# bontor_mbed_rev_f.net
KiCad netlist of a schematic drawn in EAGLE
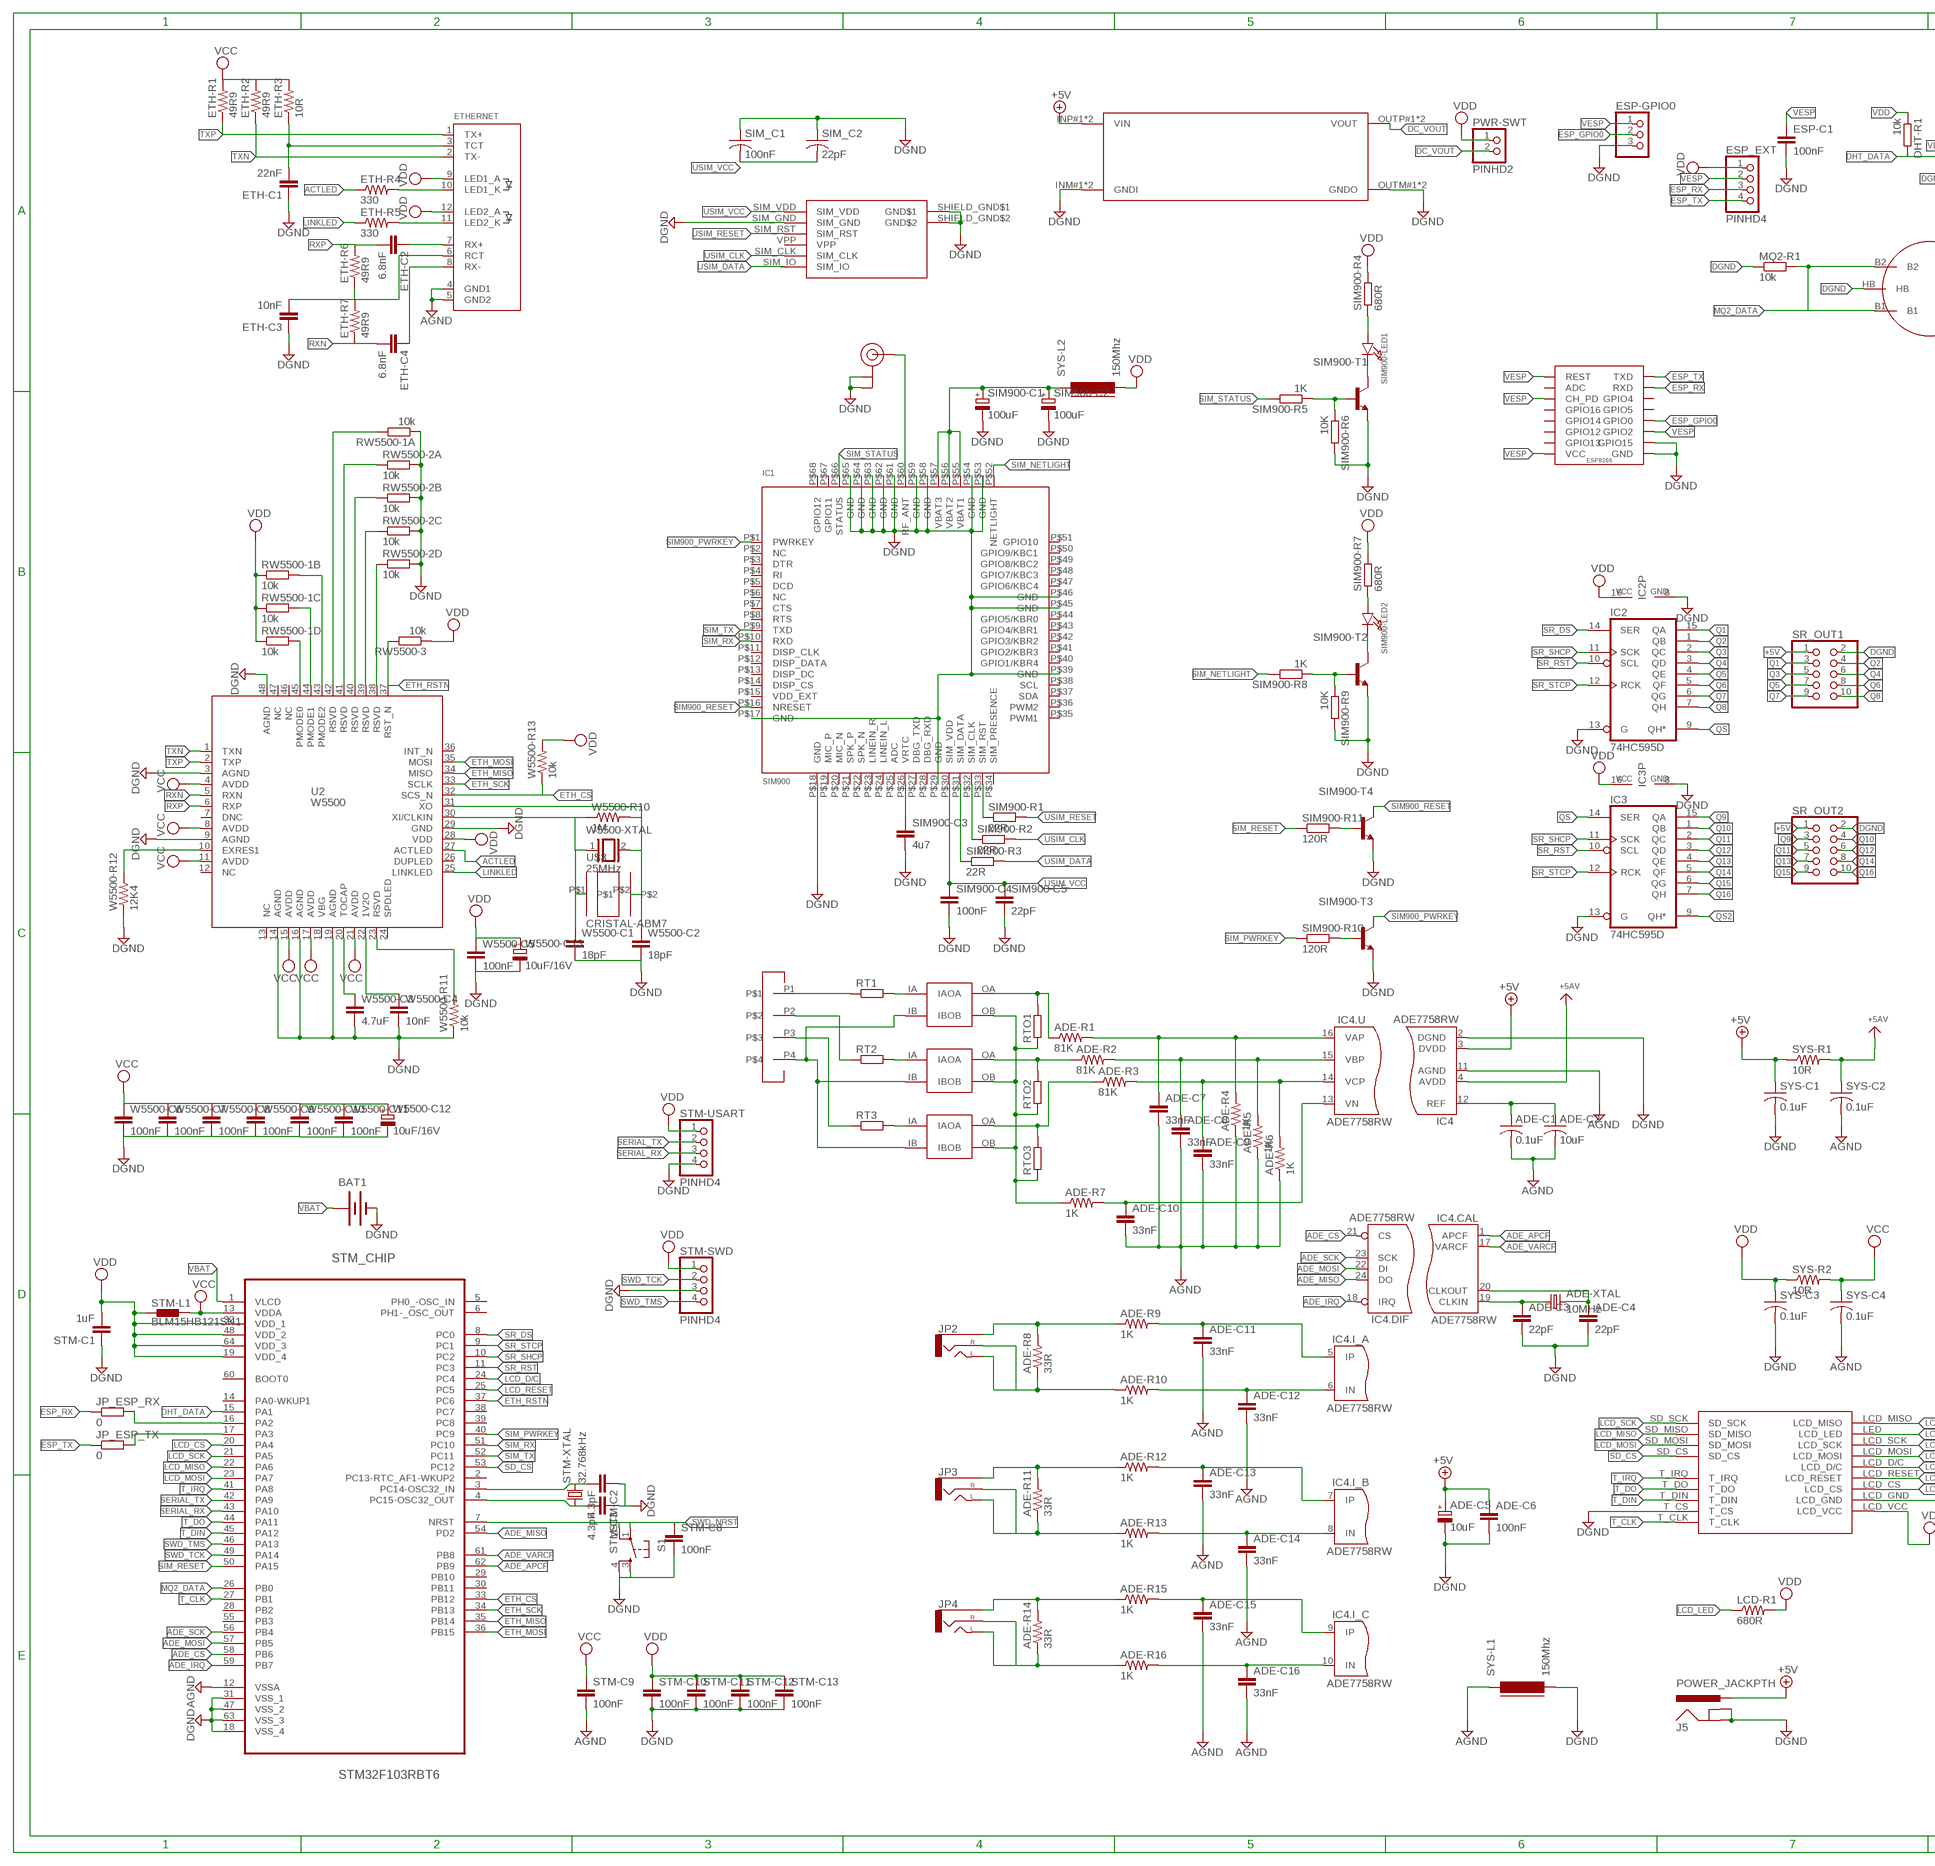
[diagram p0: schematic, sheet 1, part 1 of 2]
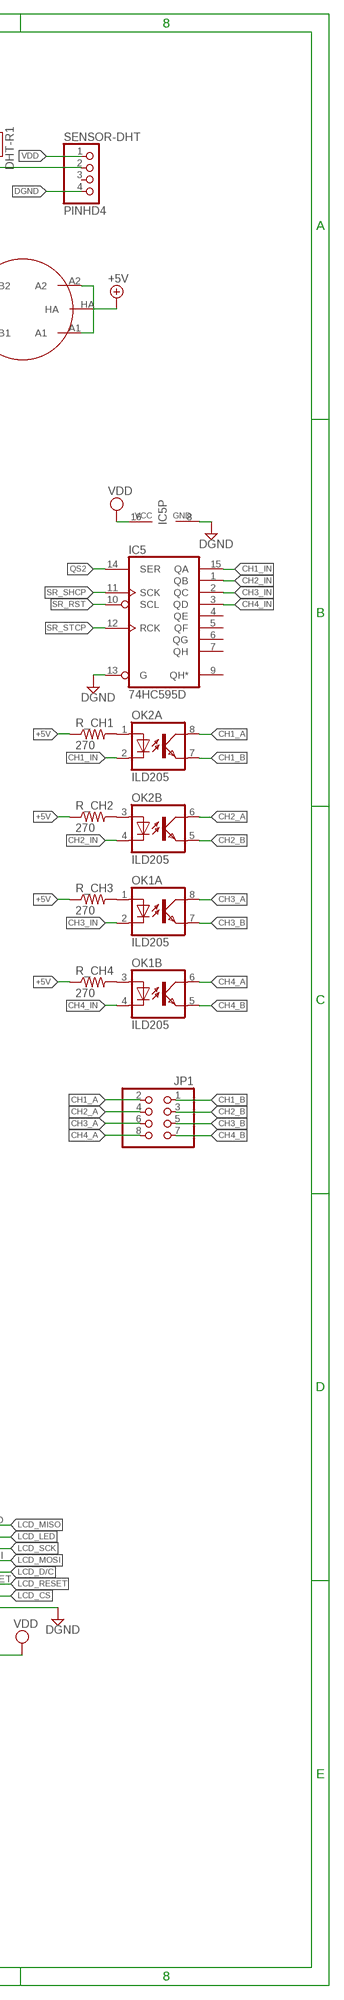
[diagram p1: schematic, sheet 1, part 2 of 2]

(export (version "E")
  (design (tool "Eeschema 10.0.6"))
  (components
    (comp (ref "ADE-C1")
      (value "0.1uF")
      (footprint "eagle-import:C0603@1")
      (libsource (lib "eagle-import") (part "C-USC0603"))
    )
    (comp (ref "ADE-C2")
      (value "10uF")
      (footprint "eagle-import:C0805K")
      (libsource (lib "eagle-import") (part "C-USC0805K"))
    )
    (comp (ref "ADE-C3")
      (value "22pF")
      (footprint "eagle-import:C0603")
      (libsource (lib "eagle-import") (part "C-EUC0603"))
    )
    (comp (ref "ADE-C4")
      (value "22pF")
      (footprint "eagle-import:C0603")
      (libsource (lib "eagle-import") (part "C-EUC0603"))
    )
    (comp (ref "ADE-C5")
      (value "10uF")
      (footprint "eagle-import:153CLV-0605")
      (libsource (lib "eagle-import") (part "CPOL-EU153CLV-0605"))
    )
    (comp (ref "ADE-C6")
      (value "100nF")
      (footprint "eagle-import:C0603")
      (libsource (lib "eagle-import") (part "C-EUC0603"))
    )
    (comp (ref "ADE-C7")
      (value "33nF")
      (footprint "eagle-import:0603-CAP")
      (libsource (lib "eagle-import") (part "CAP0603-CAP"))
    )
    (comp (ref "ADE-C8")
      (value "33nF")
      (footprint "eagle-import:0603-CAP")
      (libsource (lib "eagle-import") (part "CAP0603-CAP"))
    )
    (comp (ref "ADE-C9")
      (value "33nF")
      (footprint "eagle-import:0603-CAP")
      (libsource (lib "eagle-import") (part "CAP0603-CAP"))
    )
    (comp (ref "ADE-C10")
      (value "33nF")
      (footprint "eagle-import:0603-CAP")
      (libsource (lib "eagle-import") (part "CAP0603-CAP"))
    )
    (comp (ref "ADE-C11")
      (value "33nF")
      (footprint "eagle-import:0603-CAP")
      (libsource (lib "eagle-import") (part "CAP0603-CAP"))
    )
    (comp (ref "ADE-C12")
      (value "33nF")
      (footprint "eagle-import:0603-CAP")
      (libsource (lib "eagle-import") (part "CAP0603-CAP"))
    )
    (comp (ref "ADE-C13")
      (value "33nF")
      (footprint "eagle-import:0603-CAP")
      (libsource (lib "eagle-import") (part "CAP0603-CAP"))
    )
    (comp (ref "ADE-C14")
      (value "33nF")
      (footprint "eagle-import:0603-CAP")
      (libsource (lib "eagle-import") (part "CAP0603-CAP"))
    )
    (comp (ref "ADE-C15")
      (value "33nF")
      (footprint "eagle-import:0603-CAP")
      (libsource (lib "eagle-import") (part "CAP0603-CAP"))
    )
    (comp (ref "ADE-C16")
      (value "33nF")
      (footprint "eagle-import:0603-CAP")
      (libsource (lib "eagle-import") (part "CAP0603-CAP"))
    )
    (comp (ref "ADE-R1")
      (value "81K")
      (footprint "eagle-import:0603-RES")
      (libsource (lib "eagle-import") (part "RESISTOR0603-RES"))
    )
    (comp (ref "ADE-R2")
      (value "81K")
      (footprint "eagle-import:0603-RES")
      (libsource (lib "eagle-import") (part "RESISTOR0603-RES"))
    )
    (comp (ref "ADE-R3")
      (value "81K")
      (footprint "eagle-import:0603-RES")
      (libsource (lib "eagle-import") (part "RESISTOR0603-RES"))
    )
    (comp (ref "ADE-R4")
      (value "1K")
      (footprint "eagle-import:0603-RES")
      (libsource (lib "eagle-import") (part "RESISTOR0603-RES"))
    )
    (comp (ref "ADE-R5")
      (value "1K")
      (footprint "eagle-import:0603-RES")
      (libsource (lib "eagle-import") (part "RESISTOR0603-RES"))
    )
    (comp (ref "ADE-R6")
      (value "1K")
      (footprint "eagle-import:0603-RES")
      (libsource (lib "eagle-import") (part "RESISTOR0603-RES"))
    )
    (comp (ref "ADE-R7")
      (value "1K")
      (footprint "eagle-import:0603-RES")
      (libsource (lib "eagle-import") (part "RESISTOR0603-RES"))
    )
    (comp (ref "ADE-R8")
      (value "33R")
      (footprint "eagle-import:0603-RES")
      (libsource (lib "eagle-import") (part "RESISTOR0603-RES"))
    )
    (comp (ref "ADE-R9")
      (value "1K")
      (footprint "eagle-import:0603-RES")
      (libsource (lib "eagle-import") (part "RESISTOR0603-RES"))
    )
    (comp (ref "ADE-R10")
      (value "1K")
      (footprint "eagle-import:0603-RES")
      (libsource (lib "eagle-import") (part "RESISTOR0603-RES"))
    )
    (comp (ref "ADE-R11")
      (value "33R")
      (footprint "eagle-import:0603-RES")
      (libsource (lib "eagle-import") (part "RESISTOR0603-RES"))
    )
    (comp (ref "ADE-R12")
      (value "1K")
      (footprint "eagle-import:0603-RES")
      (libsource (lib "eagle-import") (part "RESISTOR0603-RES"))
    )
    (comp (ref "ADE-R13")
      (value "1K")
      (footprint "eagle-import:0603-RES")
      (libsource (lib "eagle-import") (part "RESISTOR0603-RES"))
    )
    (comp (ref "ADE-R14")
      (value "33R")
      (footprint "eagle-import:0603-RES")
      (libsource (lib "eagle-import") (part "RESISTOR0603-RES"))
    )
    (comp (ref "ADE-R15")
      (value "1K")
      (footprint "eagle-import:0603-RES")
      (libsource (lib "eagle-import") (part "RESISTOR0603-RES"))
    )
    (comp (ref "ADE-R16")
      (value "1K")
      (footprint "eagle-import:0603-RES")
      (libsource (lib "eagle-import") (part "RESISTOR0603-RES"))
    )
    (comp (ref "ADE-XTAL")
      (value "10MHz")
      (footprint "eagle-import:HC49US")
      (libsource (lib "eagle-import") (part "CRYSTALHC49US"))
    )
    (comp (ref "BAT1")
      (value "BATTERY12MM")
      (footprint "eagle-import:BATTCON_12MM")
      (libsource (lib "eagle-import") (part "BATTERY12MM"))
    )
    (comp (ref "DCDC-3.5V")
      (value "DCDCMODULE_SMALL")
      (footprint "eagle-import:DCDCMODULE-SMALL")
      (libsource (lib "eagle-import") (part "DCDCMODULE_SMALL"))
    )
    (comp (ref "DHT-R1")
      (value "10k")
      (footprint "eagle-import:R0603")
      (libsource (lib "eagle-import") (part "resistor_R-EU_R0603"))
    )
    (comp (ref "ESP-C1")
      (value "100nF")
      (footprint "eagle-import:C0603")
      (libsource (lib "eagle-import") (part "C-EUC0603"))
    )
    (comp (ref "ESP-GPIO0")
      (value "PINHD-1X3")
      (footprint "eagle-import:1X03")
      (libsource (lib "eagle-import") (part "PINHD-1X3"))
    )
    (comp (ref "ESP_EXT")
      (value "PINHD4")
      (footprint "eagle-import:PINHD4")
      (libsource (lib "eagle-import") (part "PINHD4"))
    )
    (comp (ref "ETH-C1")
      (value "22nF")
      (footprint "eagle-import:C0603")
      (libsource (lib "eagle-import") (part "C-EUC0603"))
    )
    (comp (ref "ETH-C2")
      (value "6.8nF")
      (footprint "eagle-import:C0603")
      (libsource (lib "eagle-import") (part "C-EUC0603"))
    )
    (comp (ref "ETH-C3")
      (value "10nF")
      (footprint "eagle-import:C0603")
      (libsource (lib "eagle-import") (part "C-EUC0603"))
    )
    (comp (ref "ETH-C4")
      (value "6.8nF")
      (footprint "eagle-import:C0603")
      (libsource (lib "eagle-import") (part "C-EUC0603"))
    )
    (comp (ref "ETH-R1")
      (value "49R9")
      (footprint "eagle-import:R0603")
      (libsource (lib "eagle-import") (part "R-US_R0603"))
    )
    (comp (ref "ETH-R2")
      (value "49R9")
      (footprint "eagle-import:R0603")
      (libsource (lib "eagle-import") (part "R-US_R0603"))
    )
    (comp (ref "ETH-R3")
      (value "10R")
      (footprint "eagle-import:R0603")
      (libsource (lib "eagle-import") (part "R-US_R0603"))
    )
    (comp (ref "ETH-R4")
      (value "330")
      (footprint "eagle-import:R0603")
      (libsource (lib "eagle-import") (part "R-US_R0603"))
    )
    (comp (ref "ETH-R5")
      (value "330")
      (footprint "eagle-import:R0603")
      (libsource (lib "eagle-import") (part "R-US_R0603"))
    )
    (comp (ref "ETH-R6")
      (value "49R9")
      (footprint "eagle-import:R0603")
      (libsource (lib "eagle-import") (part "R-US_R0603"))
    )
    (comp (ref "ETH-R7")
      (value "49R9")
      (footprint "eagle-import:R0603")
      (libsource (lib "eagle-import") (part "R-US_R0603"))
    )
    (comp (ref "ETHERNET")
      (value "RJ45J0026D21BNL")
      (footprint "eagle-import:RJ45_PULSEJACK")
      (libsource (lib "eagle-import") (part "RJ45J0026D21BNL"))
    )
    (comp (ref "IC1")
      (value "SIM900")
      (footprint "eagle-import:SIM900_SMT")
      (libsource (lib "eagle-import") (part "GSM_SIM900_LITERAL"))
    )
    (comp (ref "IC2")
      (value "74HC595D")
      (footprint "eagle-import:SO16")
      (libsource (lib "eagle-import") (part "74595DHC"))
    )
    (comp (ref "IC3")
      (value "74HC595D")
      (footprint "eagle-import:SO16")
      (libsource (lib "eagle-import") (part "74595DHC"))
    )
    (comp (ref "IC4")
      (value "ADE7758RW")
      (footprint "eagle-import:SOIC24")
      (libsource (lib "eagle-import") (part "ADE7758RW"))
    )
    (comp (ref "IC5")
      (value "74HC595D")
      (footprint "eagle-import:SO16")
      (libsource (lib "eagle-import") (part "74595DHC"))
    )
    (comp (ref "J5")
      (value "POWER_JACKPTH")
      (footprint "eagle-import:POWER_JACK_PTH")
      (libsource (lib "eagle-import") (part "POWER_JACKPTH"))
    )
    (comp (ref "JP1")
      (value "PINHD-2X4")
      (footprint "eagle-import:2X04")
      (libsource (lib "eagle-import") (part "PINHD-2X4"))
    )
    (comp (ref "JP2")
      (value "AUDIO-JACKSMD2")
      (footprint "eagle-import:AUDIO-JACK-3.5MM-SMD")
      (libsource (lib "eagle-import") (part "AUDIO-JACKSMD2"))
    )
    (comp (ref "JP3")
      (value "AUDIO-JACKSMD2")
      (footprint "eagle-import:AUDIO-JACK-3.5MM-SMD")
      (libsource (lib "eagle-import") (part "AUDIO-JACKSMD2"))
    )
    (comp (ref "JP4")
      (value "AUDIO-JACKSMD2")
      (footprint "eagle-import:AUDIO-JACK-3.5MM-SMD")
      (libsource (lib "eagle-import") (part "AUDIO-JACKSMD2"))
    )
    (comp (ref "JP_ESP_RX")
      (value "0")
      (footprint "eagle-import:R0201")
      (libsource (lib "eagle-import") (part "R-EU_R0201"))
    )
    (comp (ref "JP_ESP_TX")
      (value "0")
      (footprint "eagle-import:R0201")
      (libsource (lib "eagle-import") (part "R-EU_R0201"))
    )
    (comp (ref "LCD-R1")
      (value "680R")
      (footprint "eagle-import:0603-RES")
      (libsource (lib "eagle-import") (part "RESISTOR0603-RES"))
    )
    (comp (ref "MQ2-R1")
      (value "10k")
      (footprint "eagle-import:R0603")
      (libsource (lib "eagle-import") (part "resistor_R-EU_R0603"))
    )
    (comp (ref "OK1")
      (value "ILD205")
      (footprint "eagle-import:SOIC08")
      (fields (field (name "MF") "VISHAY/TELEFUNKEN") (field (name "MPN") "ILD205T"))
      (libsource (lib "eagle-import") (part "ILD205"))
    )
    (comp (ref "OK2")
      (value "ILD205")
      (footprint "eagle-import:SOIC08")
      (fields (field (name "MF") "VISHAY/TELEFUNKEN") (field (name "MPN") "ILD205T"))
      (libsource (lib "eagle-import") (part "ILD205"))
    )
    (comp (ref "PWR-SWT")
      (value "PINHD2")
      (footprint "eagle-import:PINHD2")
      (libsource (lib "eagle-import") (part "PINHD2"))
    )
    (comp (ref "RT1")
      (value "R-EU_0309/V")
      (footprint "eagle-import:0309V")
      (libsource (lib "eagle-import") (part "R-EU_0309/V"))
    )
    (comp (ref "RT2")
      (value "R-EU_0309/V")
      (footprint "eagle-import:0309V")
      (libsource (lib "eagle-import") (part "R-EU_0309/V"))
    )
    (comp (ref "RT3")
      (value "R-EU_0309/V")
      (footprint "eagle-import:0309V")
      (libsource (lib "eagle-import") (part "R-EU_0309/V"))
    )
    (comp (ref "RTO1")
      (value "R-EU_0309/12")
      (footprint "eagle-import:0309_12")
      (libsource (lib "eagle-import") (part "R-EU_0309/12"))
    )
    (comp (ref "RTO2")
      (value "R-EU_0309/12")
      (footprint "eagle-import:0309_12")
      (libsource (lib "eagle-import") (part "R-EU_0309/12"))
    )
    (comp (ref "RTO3")
      (value "R-EU_0309/12")
      (footprint "eagle-import:0309_12")
      (libsource (lib "eagle-import") (part "R-EU_0309/12"))
    )
    (comp (ref "RW5500-1")
      (value "10k")
      (footprint "eagle-import:RN8P-4R-CRA06S")
      (libsource (lib "eagle-import") (part "RESISTOR_ARRAY_4"))
    )
    (comp (ref "RW5500-2")
      (value "10k")
      (footprint "eagle-import:RN8P-4R-CRA06S")
      (libsource (lib "eagle-import") (part "RESISTOR_ARRAY_4"))
    )
    (comp (ref "RW5500-3")
      (value "10k")
      (footprint "eagle-import:R0603")
      (libsource (lib "eagle-import") (part "R-EU_R0603"))
    )
    (comp (ref "R_CH1")
      (value "270")
      (footprint "eagle-import:0603-RES")
      (libsource (lib "eagle-import") (part "RESISTOR0603-RES"))
    )
    (comp (ref "R_CH2")
      (value "270")
      (footprint "eagle-import:0603-RES")
      (libsource (lib "eagle-import") (part "RESISTOR0603-RES"))
    )
    (comp (ref "R_CH3")
      (value "270")
      (footprint "eagle-import:0603-RES")
      (libsource (lib "eagle-import") (part "RESISTOR0603-RES"))
    )
    (comp (ref "R_CH4")
      (value "270")
      (footprint "eagle-import:0603-RES")
      (libsource (lib "eagle-import") (part "RESISTOR0603-RES"))
    )
    (comp (ref "S1")
      (value "TAC_SWITCHSMD")
      (footprint "eagle-import:TACTILE-SWITCH-SMD")
      (libsource (lib "eagle-import") (part "TAC_SWITCHSMD"))
    )
    (comp (ref "SENSOR-DHT")
      (value "PINHD4")
      (footprint "eagle-import:PINHD4")
      (libsource (lib "eagle-import") (part "PINHD4"))
    )
    (comp (ref "SENSOR-MQ2")
      (value "METHANE_SENSOR")
      (footprint "eagle-import:MQ-3")
      (libsource (lib "eagle-import") (part "METHANE_SENSOR"))
    )
    (comp (ref "SIM900-C1")
      (value "100uF")
      (footprint "eagle-import:153CLV-0605")
      (libsource (lib "eagle-import") (part "CPOL-EU153CLV-0605"))
    )
    (comp (ref "SIM900-C2")
      (value "100uF")
      (footprint "eagle-import:153CLV-0605")
      (libsource (lib "eagle-import") (part "CPOL-EU153CLV-0605"))
    )
    (comp (ref "SIM900-C3")
      (value "4u7")
      (footprint "eagle-import:C0603")
      (libsource (lib "eagle-import") (part "C-EUC0603"))
    )
    (comp (ref "SIM900-C4")
      (value "100nF")
      (footprint "eagle-import:C0603")
      (libsource (lib "eagle-import") (part "C-EUC0603"))
    )
    (comp (ref "SIM900-C5")
      (value "22pF")
      (footprint "eagle-import:C0603")
      (libsource (lib "eagle-import") (part "C-EUC0603"))
    )
    (comp (ref "SIM900-LED1")
      (value "LED0805_NOOUTLINE")
      (footprint "eagle-import:CHIPLED_0805_NOOUTLINE")
      (libsource (lib "eagle-import") (part "LED0805_NOOUTLINE"))
    )
    (comp (ref "SIM900-LED2")
      (value "LED0805_NOOUTLINE")
      (footprint "eagle-import:CHIPLED_0805_NOOUTLINE")
      (libsource (lib "eagle-import") (part "LED0805_NOOUTLINE"))
    )
    (comp (ref "SIM900-R1")
      (value "22R")
      (footprint "eagle-import:R0603")
      (libsource (lib "eagle-import") (part "R-EU_R0603"))
    )
    (comp (ref "SIM900-R2")
      (value "22R")
      (footprint "eagle-import:R0603")
      (libsource (lib "eagle-import") (part "R-EU_R0603"))
    )
    (comp (ref "SIM900-R3")
      (value "22R")
      (footprint "eagle-import:R0603")
      (libsource (lib "eagle-import") (part "R-EU_R0603"))
    )
    (comp (ref "SIM900-R4")
      (value "680R")
      (footprint "eagle-import:R0603")
      (libsource (lib "eagle-import") (part "R-EU_R0603"))
    )
    (comp (ref "SIM900-R5")
      (value "1K")
      (footprint "eagle-import:R0603")
      (libsource (lib "eagle-import") (part "R-EU_R0603"))
    )
    (comp (ref "SIM900-R6")
      (value "10K")
      (footprint "eagle-import:R0603")
      (libsource (lib "eagle-import") (part "R-EU_R0603"))
    )
    (comp (ref "SIM900-R7")
      (value "680R")
      (footprint "eagle-import:R0603")
      (libsource (lib "eagle-import") (part "R-EU_R0603"))
    )
    (comp (ref "SIM900-R8")
      (value "1K")
      (footprint "eagle-import:R0603")
      (libsource (lib "eagle-import") (part "R-EU_R0603"))
    )
    (comp (ref "SIM900-R9")
      (value "10K")
      (footprint "eagle-import:R0603")
      (libsource (lib "eagle-import") (part "R-EU_R0603"))
    )
    (comp (ref "SIM900-R10")
      (value "120R")
      (footprint "eagle-import:R0603")
      (libsource (lib "eagle-import") (part "resistor_R-EU_R0603"))
    )
    (comp (ref "SIM900-R11")
      (value "120R")
      (footprint "eagle-import:R0603")
      (libsource (lib "eagle-import") (part "resistor_R-EU_R0603"))
    )
    (comp (ref "SIM900-T1")
      (value "MMBT2222ALT1-NPN-SOT23-BEC")
      (footprint "eagle-import:SOT23-BEC")
      (libsource (lib "eagle-import") (part "-NPN-SOT23-BECMMBT2222ALT1"))
    )
    (comp (ref "SIM900-T2")
      (value "MMBT2222ALT1-NPN-SOT23-BEC")
      (footprint "eagle-import:SOT23-BEC")
      (libsource (lib "eagle-import") (part "-NPN-SOT23-BECMMBT2222ALT1"))
    )
    (comp (ref "SIM900-T3")
      (value "MMBT2222ALT1-NPN-SOT23-BEC")
      (footprint "eagle-import:SOT23-BEC")
      (libsource (lib "eagle-import") (part "transistor-neu-to92_-NPN-SOT23-BECMMBT2222ALT1"))
    )
    (comp (ref "SIM900-T4")
      (value "MMBT2222ALT1-NPN-SOT23-BEC")
      (footprint "eagle-import:SOT23-BEC")
      (libsource (lib "eagle-import") (part "transistor-neu-to92_-NPN-SOT23-BECMMBT2222ALT1"))
    )
    (comp (ref "SIM_C1")
      (value "100nF")
      (footprint "eagle-import:C0603K")
      (libsource (lib "eagle-import") (part "C-USC0603K"))
    )
    (comp (ref "SIM_C2")
      (value "22pF")
      (footprint "eagle-import:C0603K")
      (libsource (lib "eagle-import") (part "C-USC0603K"))
    )
    (comp (ref "SR_OUT1")
      (value "PINHD-2X5/90")
      (footprint "eagle-import:2X05_90")
      (libsource (lib "eagle-import") (part "PINHD-2X5/90"))
    )
    (comp (ref "SR_OUT2")
      (value "PINHD-2X5/90")
      (footprint "eagle-import:2X05_90")
      (libsource (lib "eagle-import") (part "PINHD-2X5/90"))
    )
    (comp (ref "STM-C1")
      (value "1uF")
      (footprint "eagle-import:C0603")
      (libsource (lib "eagle-import") (part "C-EUC0603"))
    )
    (comp (ref "STM-C2")
      (value "4.3pF")
      (footprint "eagle-import:C0603")
      (libsource (lib "eagle-import") (part "C-EUC0603"))
    )
    (comp (ref "STM-C3")
      (value "4.3pF")
      (footprint "eagle-import:C0603")
      (libsource (lib "eagle-import") (part "C-EUC0603"))
    )
    (comp (ref "STM-C8")
      (value "100nF")
      (footprint "eagle-import:C0603")
      (libsource (lib "eagle-import") (part "C-EUC0603"))
    )
    (comp (ref "STM-C9")
      (value "100nF")
      (footprint "eagle-import:C0603")
      (libsource (lib "eagle-import") (part "C-EUC0603"))
    )
    (comp (ref "STM-C10")
      (value "100nF")
      (footprint "eagle-import:C0603")
      (libsource (lib "eagle-import") (part "C-EUC0603"))
    )
    (comp (ref "STM-C11")
      (value "100nF")
      (footprint "eagle-import:C0603")
      (libsource (lib "eagle-import") (part "C-EUC0603"))
    )
    (comp (ref "STM-C12")
      (value "100nF")
      (footprint "eagle-import:C0603")
      (libsource (lib "eagle-import") (part "C-EUC0603"))
    )
    (comp (ref "STM-C13")
      (value "100nF")
      (footprint "eagle-import:C0603")
      (libsource (lib "eagle-import") (part "C-EUC0603"))
    )
    (comp (ref "STM-L1")
      (value "BLM15HB121SN1")
      (footprint "eagle-import:0402")
      (libsource (lib "eagle-import") (part "BLM15HB121SN1"))
    )
    (comp (ref "STM-SWD")
      (value "PINHD4")
      (footprint "eagle-import:PINHD4")
      (libsource (lib "eagle-import") (part "PINHD4"))
    )
    (comp (ref "STM-USART")
      (value "PINHD4")
      (footprint "eagle-import:PINHD4")
      (libsource (lib "eagle-import") (part "PINHD4"))
    )
    (comp (ref "STM-XTAL")
      (value "32.768kHz")
      (footprint "eagle-import:TC26H")
      (libsource (lib "eagle-import") (part "CRYSTALTC26H"))
    )
    (comp (ref "STM_CHIP")
      (value "STM32F103RBT6")
      (footprint "eagle-import:QFP50P1200X1200X160-64N")
      (fields (field (name "MPN") "STM32L152RBT6"))
      (libsource (lib "eagle-import") (part "STM32L152RBT6"))
    )
    (comp (ref "SYS-C1")
      (value "0.1uF")
      (footprint "eagle-import:C0603@1")
      (libsource (lib "eagle-import") (part "C-USC0603"))
    )
    (comp (ref "SYS-C2")
      (value "0.1uF")
      (footprint "eagle-import:C0603@1")
      (libsource (lib "eagle-import") (part "C-USC0603"))
    )
    (comp (ref "SYS-C3")
      (value "0.1uF")
      (footprint "eagle-import:C0603@1")
      (libsource (lib "eagle-import") (part "C-USC0603"))
    )
    (comp (ref "SYS-C4")
      (value "0.1uF")
      (footprint "eagle-import:C0603@1")
      (libsource (lib "eagle-import") (part "C-USC0603"))
    )
    (comp (ref "SYS-L1")
      (value "150Mhz")
      (footprint "eagle-import:FB805")
      (libsource (lib "eagle-import") (part "FERRITE-0805"))
    )
    (comp (ref "SYS-L2")
      (value "150Mhz")
      (footprint "eagle-import:FB805")
      (libsource (lib "eagle-import") (part "FERRITE-0805"))
    )
    (comp (ref "SYS-R1")
      (value "10R")
      (footprint "eagle-import:0603-RES")
      (libsource (lib "eagle-import") (part "RESISTOR0603-RES"))
    )
    (comp (ref "SYS-R2")
      (value "10R")
      (footprint "eagle-import:0603-RES")
      (libsource (lib "eagle-import") (part "RESISTOR0603-RES"))
    )
    (comp (ref "U$3")
      (value "CRISTAL-ABM7")
      (footprint "eagle-import:CRISTAL-ABM7")
      (libsource (lib "eagle-import") (part "CRISTAL-ABM7"))
    )
    (comp (ref "U$5")
      (value "ESP8266WI12")
      (footprint "eagle-import:WI12")
      (libsource (lib "eagle-import") (part "ESP8266WI12"))
    )
    (comp (ref "U$7")
      (value "U.FL")
      (footprint "eagle-import:U.FL")
      (libsource (lib "eagle-import") (part "U.FL"))
    )
    (comp (ref "U$8")
      (value "SIM_HOLDER")
      (footprint "eagle-import:SIMHOLDER-PUSHPUSH")
      (libsource (lib "eagle-import") (part "SIM_HOLDER"))
    )
    (comp (ref "U$9")
      (value "TRANSFORMER")
      (footprint "eagle-import:TV16")
      (libsource (lib "eagle-import") (part "TRANSFORMER"))
    )
    (comp (ref "U$10")
      (value "TRANSFORMER")
      (footprint "eagle-import:TV16")
      (libsource (lib "eagle-import") (part "TRANSFORMER"))
    )
    (comp (ref "U$11")
      (value "TRANSFORMER")
      (footprint "eagle-import:TV16")
      (libsource (lib "eagle-import") (part "TRANSFORMER"))
    )
    (comp (ref "U$12")
      (value "TERMINAL_BLOCK")
      (footprint "eagle-import:TERMINAL-RIGHT-ANGLE")
      (libsource (lib "eagle-import") (part "TERMINAL_BLOCK"))
    )
    (comp (ref "U$13")
      (value "LCD_2.4")
      (footprint "eagle-import:LCD_TOUCH_2-4")
      (libsource (lib "eagle-import") (part "LCD_2.4"))
    )
    (comp (ref "U2")
      (value "W5500")
      (footprint "eagle-import:W5500")
      (libsource (lib "eagle-import") (part "W5500"))
    )
    (comp (ref "W5500-C1")
      (value "18pF")
      (footprint "eagle-import:C0603")
      (libsource (lib "eagle-import") (part "C-EUC0603"))
    )
    (comp (ref "W5500-C2")
      (value "18pF")
      (footprint "eagle-import:C0603")
      (libsource (lib "eagle-import") (part "C-EUC0603"))
    )
    (comp (ref "W5500-C3")
      (value "4.7uF")
      (footprint "eagle-import:C0603")
      (libsource (lib "eagle-import") (part "C-EUC0603"))
    )
    (comp (ref "W5500-C4")
      (value "10nF")
      (footprint "eagle-import:C0603")
      (libsource (lib "eagle-import") (part "C-EUC0603"))
    )
    (comp (ref "W5500-C5")
      (value "100nF")
      (footprint "eagle-import:C0603")
      (libsource (lib "eagle-import") (part "C-EUC0603"))
    )
    (comp (ref "W5500-C6")
      (value "100nF")
      (footprint "eagle-import:C0603")
      (libsource (lib "eagle-import") (part "C-EUC0603"))
    )
    (comp (ref "W5500-C7")
      (value "100nF")
      (footprint "eagle-import:C0603")
      (libsource (lib "eagle-import") (part "C-EUC0603"))
    )
    (comp (ref "W5500-C8")
      (value "100nF")
      (footprint "eagle-import:C0603")
      (libsource (lib "eagle-import") (part "C-EUC0603"))
    )
    (comp (ref "W5500-C9")
      (value "100nF")
      (footprint "eagle-import:C0603")
      (libsource (lib "eagle-import") (part "C-EUC0603"))
    )
    (comp (ref "W5500-C10")
      (value "100nF")
      (footprint "eagle-import:C0603")
      (libsource (lib "eagle-import") (part "C-EUC0603"))
    )
    (comp (ref "W5500-C11")
      (value "100nF")
      (footprint "eagle-import:C0603")
      (libsource (lib "eagle-import") (part "C-EUC0603"))
    )
    (comp (ref "W5500-C12")
      (value "10uF/16V")
      (footprint "eagle-import:153CLV-0605")
      (libsource (lib "eagle-import") (part "CPOL-EU153CLV-0605"))
    )
    (comp (ref "W5500-C13")
      (value "10uF/16V")
      (footprint "eagle-import:153CLV-0605")
      (libsource (lib "eagle-import") (part "CPOL-EU153CLV-0605"))
    )
    (comp (ref "W5500-R10")
      (value "1M")
      (footprint "eagle-import:R0603")
      (libsource (lib "eagle-import") (part "R-US_R0603"))
    )
    (comp (ref "W5500-R11")
      (value "10k")
      (footprint "eagle-import:R0603")
      (libsource (lib "eagle-import") (part "R-US_R0603"))
    )
    (comp (ref "W5500-R12")
      (value "12K4")
      (footprint "eagle-import:R0805")
      (libsource (lib "eagle-import") (part "R-US_R0805"))
    )
    (comp (ref "W5500-R13")
      (value "10k")
      (footprint "eagle-import:R0603")
      (libsource (lib "eagle-import") (part "R-US_R0603"))
    )
    (comp (ref "W5500-XTAL")
      (value "25MHz")
      (footprint "eagle-import:QS")
      (libsource (lib "eagle-import") (part "XTAL/S"))
    )
  )
  (nets
    (net (code "1") (name "+5AV") (class "Default")
      (node (ref "IC4") (pin "4") (pinfunction "AVDD_4") (pintype "power_in"))
      (node (ref "SYS-C2") (pin "1") (pinfunction "1_1") (pintype "passive"))
      (node (ref "SYS-R1") (pin "2") (pinfunction "2_2") (pintype "passive"))
    )
    (net (code "2") (name "+5V") (class "Default")
      (node (ref "ADE-C5") (pin "+") (pinfunction "+_+") (pintype "passive"))
      (node (ref "ADE-C6") (pin "1") (pinfunction "1_1") (pintype "passive"))
      (node (ref "DCDC-3.5V") (pin "INP#1") (pinfunction "VIN_INP#1") (pintype "bidirectional"))
      (node (ref "DCDC-3.5V") (pin "INP#2") (pinfunction "VIN_INP#2") (pintype "bidirectional"))
      (node (ref "IC4") (pin "3") (pinfunction "DVDD_3") (pintype "power_in"))
      (node (ref "J5") (pin "PWR") (pinfunction "PWR_PWR") (pintype "bidirectional"))
      (node (ref "R_CH1") (pin "1") (pinfunction "1_1") (pintype "passive"))
      (node (ref "R_CH2") (pin "1") (pinfunction "1_1") (pintype "passive"))
      (node (ref "R_CH3") (pin "1") (pinfunction "1_1") (pintype "passive"))
      (node (ref "R_CH4") (pin "1") (pinfunction "1_1") (pintype "passive"))
      (node (ref "SENSOR-MQ2") (pin "A1") (pinfunction "A1_A1") (pintype "bidirectional"))
      (node (ref "SENSOR-MQ2") (pin "A2") (pinfunction "A2_A2") (pintype "bidirectional"))
      (node (ref "SENSOR-MQ2") (pin "HA") (pinfunction "HA_HA") (pintype "bidirectional"))
      (node (ref "SR_OUT1") (pin "1") (pinfunction "1_1") (pintype "passive"))
      (node (ref "SR_OUT2") (pin "1") (pinfunction "1_1") (pintype "passive"))
      (node (ref "SYS-C1") (pin "1") (pinfunction "1_1") (pintype "passive"))
      (node (ref "SYS-R1") (pin "1") (pinfunction "1_1") (pintype "passive"))
    )
    (net (code "3") (name "/GPIO11") (class "Default")
      (node (ref "IC1") (pin "P$67") (pinfunction "GPIO11_P$67") (pintype "power_in"))
    )
    (net (code "4") (name "/GPIO12") (class "Default")
      (node (ref "IC1") (pin "P$68") (pinfunction "GPIO12_P$68") (pintype "power_in"))
    )
    (net (code "5") (name "ACTLED") (class "Default")
      (node (ref "ETH-R4") (pin "1") (pinfunction "1_1") (pintype "passive"))
      (node (ref "U2") (pin "27") (pinfunction "ACTLED_27") (pintype "passive"))
    )
    (net (code "6") (name "ADE_APCF") (class "Default")
      (node (ref "IC4") (pin "1") (pinfunction "APCF_1") (pintype "output"))
      (node (ref "STM_CHIP") (pin "62") (pinfunction "PB9_62") (pintype "bidirectional"))
    )
    (net (code "7") (name "ADE_CS") (class "Default")
      (node (ref "IC4") (pin "21") (pinfunction "CS_21") (pintype "input"))
      (node (ref "STM_CHIP") (pin "58") (pinfunction "PB6_58") (pintype "bidirectional"))
    )
    (net (code "8") (name "ADE_IRQ") (class "Default")
      (node (ref "IC4") (pin "18") (pinfunction "IRQ_18") (pintype "output"))
      (node (ref "STM_CHIP") (pin "59") (pinfunction "PB7_59") (pintype "bidirectional"))
    )
    (net (code "9") (name "ADE_MISO") (class "Default")
      (node (ref "IC4") (pin "24") (pinfunction "DO_24") (pintype "output"))
      (node (ref "STM_CHIP") (pin "54") (pinfunction "PD2_54") (pintype "bidirectional"))
    )
    (net (code "10") (name "ADE_MOSI") (class "Default")
      (node (ref "IC4") (pin "22") (pinfunction "DI_22") (pintype "input"))
      (node (ref "STM_CHIP") (pin "57") (pinfunction "PB5_57") (pintype "bidirectional"))
    )
    (net (code "11") (name "ADE_SCK") (class "Default")
      (node (ref "IC4") (pin "23") (pinfunction "SCK_23") (pintype "input"))
      (node (ref "STM_CHIP") (pin "56") (pinfunction "PB4_56") (pintype "bidirectional"))
    )
    (net (code "12") (name "ADE_VARCF") (class "Default")
      (node (ref "IC4") (pin "17") (pinfunction "VARCF_17") (pintype "output"))
      (node (ref "STM_CHIP") (pin "61") (pinfunction "PB8_61") (pintype "bidirectional"))
    )
    (net (code "13") (name "AGND") (class "Default")
      (node (ref "ADE-C1") (pin "2") (pinfunction "2_2") (pintype "passive"))
      (node (ref "ADE-C10") (pin "2") (pinfunction "2_2") (pintype "passive"))
      (node (ref "ADE-C11") (pin "2") (pinfunction "2_2") (pintype "passive"))
      (node (ref "ADE-C12") (pin "2") (pinfunction "2_2") (pintype "passive"))
      (node (ref "ADE-C13") (pin "2") (pinfunction "2_2") (pintype "passive"))
      (node (ref "ADE-C14") (pin "2") (pinfunction "2_2") (pintype "passive"))
      (node (ref "ADE-C15") (pin "2") (pinfunction "2_2") (pintype "passive"))
      (node (ref "ADE-C16") (pin "2") (pinfunction "2_2") (pintype "passive"))
      (node (ref "ADE-C2") (pin "2") (pinfunction "2_2") (pintype "passive"))
      (node (ref "ADE-C7") (pin "2") (pinfunction "2_2") (pintype "passive"))
      (node (ref "ADE-C8") (pin "2") (pinfunction "2_2") (pintype "passive"))
      (node (ref "ADE-C9") (pin "2") (pinfunction "2_2") (pintype "passive"))
      (node (ref "ADE-R4") (pin "1") (pinfunction "1_1") (pintype "passive"))
      (node (ref "ADE-R5") (pin "1") (pinfunction "1_1") (pintype "passive"))
      (node (ref "ADE-R6") (pin "1") (pinfunction "1_1") (pintype "passive"))
      (node (ref "ETHERNET") (pin "4") (pinfunction "GND1_4") (pintype "bidirectional"))
      (node (ref "ETHERNET") (pin "5") (pinfunction "GND2_5") (pintype "bidirectional"))
      (node (ref "IC4") (pin "11") (pinfunction "AGND_11") (pintype "power_in"))
      (node (ref "STM-C9") (pin "2") (pinfunction "2_2") (pintype "passive"))
      (node (ref "STM_CHIP") (pin "12") (pinfunction "VSSA_12") (pintype "power_in"))
      (node (ref "SYS-C2") (pin "2") (pinfunction "2_2") (pintype "passive"))
      (node (ref "SYS-C4") (pin "2") (pinfunction "2_2") (pintype "passive"))
      (node (ref "SYS-L1") (pin "1") (pinfunction "1_1") (pintype "passive"))
    )
    (net (code "14") (name "CH1_A") (class "Default")
      (node (ref "JP1") (pin "2") (pinfunction "2_2") (pintype "passive"))
      (node (ref "OK2") (pin "8") (pinfunction "COL_8") (pintype "passive"))
    )
    (net (code "15") (name "CH1_B") (class "Default")
      (node (ref "JP1") (pin "1") (pinfunction "1_1") (pintype "passive"))
      (node (ref "OK2") (pin "7") (pinfunction "EMIT_7") (pintype "passive"))
    )
    (net (code "16") (name "CH1_IN") (class "Default")
      (node (ref "IC5") (pin "15") (pinfunction "QA_15") (pintype "tri_state"))
      (node (ref "OK2") (pin "2") (pinfunction "C_2") (pintype "passive"))
    )
    (net (code "17") (name "CH2_A") (class "Default")
      (node (ref "JP1") (pin "4") (pinfunction "4_4") (pintype "passive"))
      (node (ref "OK2") (pin "6") (pinfunction "COL_6") (pintype "passive"))
    )
    (net (code "18") (name "CH2_B") (class "Default")
      (node (ref "JP1") (pin "3") (pinfunction "3_3") (pintype "passive"))
      (node (ref "OK2") (pin "5") (pinfunction "EMIT_5") (pintype "passive"))
    )
    (net (code "19") (name "CH2_IN") (class "Default")
      (node (ref "IC5") (pin "1") (pinfunction "QB_1") (pintype "tri_state"))
      (node (ref "OK2") (pin "4") (pinfunction "C_4") (pintype "passive"))
    )
    (net (code "20") (name "CH3_A") (class "Default")
      (node (ref "JP1") (pin "6") (pinfunction "6_6") (pintype "passive"))
      (node (ref "OK1") (pin "8") (pinfunction "COL_8") (pintype "passive"))
    )
    (net (code "21") (name "CH3_B") (class "Default")
      (node (ref "JP1") (pin "5") (pinfunction "5_5") (pintype "passive"))
      (node (ref "OK1") (pin "7") (pinfunction "EMIT_7") (pintype "passive"))
    )
    (net (code "22") (name "CH3_IN") (class "Default")
      (node (ref "IC5") (pin "2") (pinfunction "QC_2") (pintype "tri_state"))
      (node (ref "OK1") (pin "2") (pinfunction "C_2") (pintype "passive"))
    )
    (net (code "23") (name "CH4_A") (class "Default")
      (node (ref "JP1") (pin "8") (pinfunction "8_8") (pintype "passive"))
      (node (ref "OK1") (pin "6") (pinfunction "COL_6") (pintype "passive"))
    )
    (net (code "24") (name "CH4_B") (class "Default")
      (node (ref "JP1") (pin "7") (pinfunction "7_7") (pintype "passive"))
      (node (ref "OK1") (pin "5") (pinfunction "EMIT_5") (pintype "passive"))
    )
    (net (code "25") (name "CH4_IN") (class "Default")
      (node (ref "IC5") (pin "3") (pinfunction "QD_3") (pintype "tri_state"))
      (node (ref "OK1") (pin "4") (pinfunction "C_4") (pintype "passive"))
    )
    (net (code "26") (name "DC_VOUT") (class "Default")
      (node (ref "DCDC-3.5V") (pin "OUTP#1") (pinfunction "VOUT_OUTP#1") (pintype "bidirectional"))
      (node (ref "DCDC-3.5V") (pin "OUTP#2") (pinfunction "VOUT_OUTP#2") (pintype "bidirectional"))
      (node (ref "PWR-SWT") (pin "2") (pinfunction "2_2") (pintype "passive"))
    )
    (net (code "27") (name "DGND") (class "Default")
      (node (ref "ADE-C3") (pin "2") (pinfunction "2_2") (pintype "passive"))
      (node (ref "ADE-C4") (pin "2") (pinfunction "2_2") (pintype "passive"))
      (node (ref "ADE-C5") (pin "-") (pinfunction "-_-") (pintype "passive"))
      (node (ref "ADE-C6") (pin "2") (pinfunction "2_2") (pintype "passive"))
      (node (ref "BAT1") (pin "GND") (pinfunction "-_GND") (pintype "power_in"))
      (node (ref "DCDC-3.5V") (pin "INM#1") (pinfunction "GNDI_INM#1") (pintype "bidirectional"))
      (node (ref "DCDC-3.5V") (pin "INM#2") (pinfunction "GNDI_INM#2") (pintype "bidirectional"))
      (node (ref "DCDC-3.5V") (pin "OUTM#1") (pinfunction "GNDO_OUTM#1") (pintype "bidirectional"))
      (node (ref "DCDC-3.5V") (pin "OUTM#2") (pinfunction "GNDO_OUTM#2") (pintype "bidirectional"))
      (node (ref "ESP-C1") (pin "2") (pinfunction "2_2") (pintype "passive"))
      (node (ref "ESP-GPIO0") (pin "3") (pinfunction "3_3") (pintype "passive"))
      (node (ref "ETH-C1") (pin "1") (pinfunction "1_1") (pintype "passive"))
      (node (ref "ETH-C3") (pin "1") (pinfunction "1_1") (pintype "passive"))
      (node (ref "IC1") (pin "P$17") (pinfunction "GND_P$17") (pintype "power_in"))
      (node (ref "IC1") (pin "P$18") (pinfunction "GND_P$18") (pintype "power_in"))
      (node (ref "IC1") (pin "P$29") (pinfunction "GND_P$29") (pintype "power_in"))
      (node (ref "IC1") (pin "P$39") (pinfunction "GND_P$39") (pintype "power_in"))
      (node (ref "IC1") (pin "P$45") (pinfunction "GND_P$45") (pintype "power_in"))
      (node (ref "IC1") (pin "P$46") (pinfunction "GND_P$46") (pintype "power_in"))
      (node (ref "IC1") (pin "P$53") (pinfunction "GND_P$53") (pintype "power_in"))
      (node (ref "IC1") (pin "P$54") (pinfunction "GND_P$54") (pintype "power_in"))
      (node (ref "IC1") (pin "P$58") (pinfunction "GND_P$58") (pintype "power_in"))
      (node (ref "IC1") (pin "P$59") (pinfunction "GND_P$59") (pintype "power_in"))
      (node (ref "IC1") (pin "P$61") (pinfunction "GND_P$61") (pintype "power_in"))
      (node (ref "IC1") (pin "P$62") (pinfunction "GND_P$62") (pintype "power_in"))
      (node (ref "IC1") (pin "P$63") (pinfunction "GND_P$63") (pintype "power_in"))
      (node (ref "IC1") (pin "P$64") (pinfunction "GND_P$64") (pintype "power_in"))
      (node (ref "IC1") (pin "P$65") (pinfunction "GND_P$65") (pintype "power_in"))
      (node (ref "IC2") (pin "13") (pinfunction "G_13") (pintype "input"))
      (node (ref "IC2") (pin "8") (pinfunction "GND_8") (pintype "power_in"))
      (node (ref "IC3") (pin "13") (pinfunction "G_13") (pintype "input"))
      (node (ref "IC3") (pin "8") (pinfunction "GND_8") (pintype "power_in"))
      (node (ref "IC4") (pin "2") (pinfunction "DGND_2") (pintype "power_in"))
      (node (ref "IC5") (pin "13") (pinfunction "G_13") (pintype "input"))
      (node (ref "IC5") (pin "8") (pinfunction "GND_8") (pintype "power_in"))
      (node (ref "J5") (pin "GND") (pinfunction "GND_GND") (pintype "bidirectional"))
      (node (ref "J5") (pin "GNDBREAK") (pinfunction "GNDBREAK_GNDBREAK") (pintype "bidirectional"))
      (node (ref "MQ2-R1") (pin "1") (pinfunction "1_1") (pintype "passive"))
      (node (ref "RW5500-1") (pin "1") (pinfunction "1_1") (pintype "passive"))
      (node (ref "RW5500-2") (pin "5") (pinfunction "2_5") (pintype "passive"))
      (node (ref "RW5500-2") (pin "6") (pinfunction "2_6") (pintype "passive"))
      (node (ref "RW5500-2") (pin "7") (pinfunction "2_7") (pintype "passive"))
      (node (ref "RW5500-2") (pin "8") (pinfunction "2_8") (pintype "passive"))
      (node (ref "S1") (pin "3") (pinfunction "3_3") (pintype "passive"))
      (node (ref "S1") (pin "4") (pinfunction "4_4") (pintype "passive"))
      (node (ref "SENSOR-DHT") (pin "4") (pinfunction "4_4") (pintype "passive"))
      (node (ref "SENSOR-MQ2") (pin "HB") (pinfunction "HB_HB") (pintype "bidirectional"))
      (node (ref "SIM900-C1") (pin "-") (pinfunction "-_-") (pintype "passive"))
      (node (ref "SIM900-C2") (pin "-") (pinfunction "-_-") (pintype "passive"))
      (node (ref "SIM900-C3") (pin "2") (pinfunction "2_2") (pintype "passive"))
      (node (ref "SIM900-C4") (pin "2") (pinfunction "2_2") (pintype "passive"))
      (node (ref "SIM900-C5") (pin "2") (pinfunction "2_2") (pintype "passive"))
      (node (ref "SIM900-R6") (pin "2") (pinfunction "2_2") (pintype "passive"))
      (node (ref "SIM900-R9") (pin "2") (pinfunction "2_2") (pintype "passive"))
      (node (ref "SIM900-T1") (pin "E") (pinfunction "E_E") (pintype "passive"))
      (node (ref "SIM900-T2") (pin "E") (pinfunction "E_E") (pintype "passive"))
      (node (ref "SIM900-T3") (pin "E") (pinfunction "E_E") (pintype "passive"))
      (node (ref "SIM900-T4") (pin "E") (pinfunction "E_E") (pintype "passive"))
      (node (ref "SIM_C1") (pin "1") (pinfunction "1_1") (pintype "passive"))
      (node (ref "SIM_C2") (pin "1") (pinfunction "1_1") (pintype "passive"))
      (node (ref "SR_OUT1") (pin "2") (pinfunction "2_2") (pintype "passive"))
      (node (ref "SR_OUT2") (pin "2") (pinfunction "2_2") (pintype "passive"))
      (node (ref "STM-C1") (pin "1") (pinfunction "1_1") (pintype "passive"))
      (node (ref "STM-C10") (pin "2") (pinfunction "2_2") (pintype "passive"))
      (node (ref "STM-C11") (pin "2") (pinfunction "2_2") (pintype "passive"))
      (node (ref "STM-C12") (pin "2") (pinfunction "2_2") (pintype "passive"))
      (node (ref "STM-C13") (pin "2") (pinfunction "2_2") (pintype "passive"))
      (node (ref "STM-C2") (pin "1") (pinfunction "1_1") (pintype "passive"))
      (node (ref "STM-C3") (pin "1") (pinfunction "1_1") (pintype "passive"))
      (node (ref "STM-C8") (pin "2") (pinfunction "2_2") (pintype "passive"))
      (node (ref "STM-SWD") (pin "3") (pinfunction "3_3") (pintype "passive"))
      (node (ref "STM-USART") (pin "4") (pinfunction "4_4") (pintype "passive"))
      (node (ref "STM_CHIP") (pin "18") (pinfunction "VSS_4_18") (pintype "power_in"))
      (node (ref "STM_CHIP") (pin "31") (pinfunction "VSS_1_31") (pintype "power_in"))
      (node (ref "STM_CHIP") (pin "47") (pinfunction "VSS_2_47") (pintype "power_in"))
      (node (ref "STM_CHIP") (pin "63") (pinfunction "VSS_3_63") (pintype "power_in"))
      (node (ref "SYS-C1") (pin "2") (pinfunction "2_2") (pintype "passive"))
      (node (ref "SYS-C3") (pin "2") (pinfunction "2_2") (pintype "passive"))
      (node (ref "SYS-L1") (pin "2") (pinfunction "2_2") (pintype "passive"))
      (node (ref "U$13") (pin "LCD_GND") (pinfunction "LCD_GND_LCD_GND") (pintype "power_in"))
      (node (ref "U$13") (pin "T_CS") (pinfunction "T_CS_T_CS") (pintype "bidirectional"))
      (node (ref "U$5") (pin "GND") (pinfunction "GND_GND") (pintype "bidirectional"))
      (node (ref "U$5") (pin "GPIO15") (pinfunction "GPIO15_GPIO15") (pintype "bidirectional"))
      (node (ref "U$7") (pin "P$1") (pinfunction "GND_P$1") (pintype "bidirectional"))
      (node (ref "U$7") (pin "P$2") (pinfunction "GND_P$2") (pintype "bidirectional"))
      (node (ref "U$8") (pin "SHIELD_GND$1") (pinfunction "GND$1_SHIELD_GND$1") (pintype "bidirectional"))
      (node (ref "U$8") (pin "SHIELD_GND$2") (pinfunction "GND$2_SHIELD_GND$2") (pintype "bidirectional"))
      (node (ref "U$8") (pin "SIM_GND") (pinfunction "SIM_GND_SIM_GND") (pintype "bidirectional"))
      (node (ref "U2") (pin "14") (pinfunction "AGND_14") (pintype "passive"))
      (node (ref "U2") (pin "16") (pinfunction "AGND_16") (pintype "passive"))
      (node (ref "U2") (pin "19") (pinfunction "AGND_19") (pintype "passive"))
      (node (ref "U2") (pin "29") (pinfunction "GND_29") (pintype "passive"))
      (node (ref "U2") (pin "3") (pinfunction "AGND_3") (pintype "passive"))
      (node (ref "U2") (pin "48") (pinfunction "AGND_48") (pintype "passive"))
      (node (ref "U2") (pin "9") (pinfunction "AGND_9") (pintype "passive"))
      (node (ref "W5500-C1") (pin "2") (pinfunction "2_2") (pintype "passive"))
      (node (ref "W5500-C10") (pin "2") (pinfunction "2_2") (pintype "passive"))
      (node (ref "W5500-C11") (pin "2") (pinfunction "2_2") (pintype "passive"))
      (node (ref "W5500-C12") (pin "-") (pinfunction "-_-") (pintype "passive"))
      (node (ref "W5500-C13") (pin "-") (pinfunction "-_-") (pintype "passive"))
      (node (ref "W5500-C2") (pin "2") (pinfunction "2_2") (pintype "passive"))
      (node (ref "W5500-C3") (pin "2") (pinfunction "2_2") (pintype "passive"))
      (node (ref "W5500-C4") (pin "2") (pinfunction "2_2") (pintype "passive"))
      (node (ref "W5500-C5") (pin "2") (pinfunction "2_2") (pintype "passive"))
      (node (ref "W5500-C6") (pin "2") (pinfunction "2_2") (pintype "passive"))
      (node (ref "W5500-C7") (pin "2") (pinfunction "2_2") (pintype "passive"))
      (node (ref "W5500-C8") (pin "2") (pinfunction "2_2") (pintype "passive"))
      (node (ref "W5500-C9") (pin "2") (pinfunction "2_2") (pintype "passive"))
      (node (ref "W5500-R11") (pin "1") (pinfunction "1_1") (pintype "passive"))
      (node (ref "W5500-R12") (pin "1") (pinfunction "1_1") (pintype "passive"))
    )
    (net (code "28") (name "DHT_DATA") (class "Default")
      (node (ref "DHT-R1") (pin "2") (pinfunction "2_2") (pintype "passive"))
      (node (ref "SENSOR-DHT") (pin "2") (pinfunction "2_2") (pintype "passive"))
      (node (ref "STM_CHIP") (pin "15") (pinfunction "PA1_15") (pintype "bidirectional"))
    )
    (net (code "29") (name "ESP_GPIO0") (class "Default")
      (node (ref "ESP-GPIO0") (pin "2") (pinfunction "2_2") (pintype "passive"))
      (node (ref "U$5") (pin "GPIO00") (pinfunction "GPIO0_GPIO00") (pintype "bidirectional"))
    )
    (net (code "30") (name "ESP_RX") (class "Default")
      (node (ref "ESP_EXT") (pin "3") (pinfunction "3_3") (pintype "passive"))
      (node (ref "JP_ESP_RX") (pin "1") (pinfunction "1_1") (pintype "passive"))
      (node (ref "U$5") (pin "RXD") (pinfunction "RXD_RXD") (pintype "bidirectional"))
    )
    (net (code "31") (name "ESP_TX") (class "Default")
      (node (ref "ESP_EXT") (pin "4") (pinfunction "4_4") (pintype "passive"))
      (node (ref "JP_ESP_TX") (pin "1") (pinfunction "1_1") (pintype "passive"))
      (node (ref "U$5") (pin "TXD") (pinfunction "TXD_TXD") (pintype "bidirectional"))
    )
    (net (code "32") (name "ETH_CS") (class "Default")
      (node (ref "STM_CHIP") (pin "33") (pinfunction "PB12_33") (pintype "bidirectional"))
      (node (ref "U2") (pin "32") (pinfunction "SCS_N_32") (pintype "passive"))
      (node (ref "W5500-R13") (pin "1") (pinfunction "1_1") (pintype "passive"))
    )
    (net (code "33") (name "ETH_MISO") (class "Default")
      (node (ref "STM_CHIP") (pin "35") (pinfunction "PB14_35") (pintype "bidirectional"))
      (node (ref "U2") (pin "34") (pinfunction "MISO_34") (pintype "passive"))
    )
    (net (code "34") (name "ETH_MOSI") (class "Default")
      (node (ref "STM_CHIP") (pin "36") (pinfunction "PB15_36") (pintype "bidirectional"))
      (node (ref "U2") (pin "35") (pinfunction "MOSI_35") (pintype "passive"))
    )
    (net (code "35") (name "ETH_RSTN") (class "Default")
      (node (ref "RW5500-3") (pin "2") (pinfunction "2_2") (pintype "passive"))
      (node (ref "STM_CHIP") (pin "37") (pinfunction "PC6_37") (pintype "bidirectional"))
      (node (ref "U2") (pin "37") (pinfunction "RST_N_37") (pintype "passive"))
    )
    (net (code "36") (name "ETH_SCK") (class "Default")
      (node (ref "STM_CHIP") (pin "34") (pinfunction "PB13_34") (pintype "bidirectional"))
      (node (ref "U2") (pin "33") (pinfunction "SCLK_33") (pintype "passive"))
    )
    (net (code "37") (name "LCD_CS") (class "Default")
      (node (ref "STM_CHIP") (pin "20") (pinfunction "PA4_20") (pintype "bidirectional"))
      (node (ref "U$13") (pin "LCD_CS") (pinfunction "LCD_CS_LCD_CS") (pintype "bidirectional"))
    )
    (net (code "38") (name "LCD_D{slash}C") (class "Default")
      (node (ref "STM_CHIP") (pin "24") (pinfunction "PC4_24") (pintype "bidirectional"))
      (node (ref "U$13") (pin "LCD_D/C") (pinfunction "LCD_D/C_LCD_D/C") (pintype "bidirectional"))
    )
    (net (code "39") (name "LCD_LED") (class "Default")
      (node (ref "LCD-R1") (pin "1") (pinfunction "1_1") (pintype "passive"))
      (node (ref "U$13") (pin "LED") (pinfunction "LCD_LED_LED") (pintype "bidirectional"))
    )
    (net (code "40") (name "LCD_MISO") (class "Default")
      (node (ref "STM_CHIP") (pin "22") (pinfunction "PA6_22") (pintype "bidirectional"))
      (node (ref "U$13") (pin "LCD_MISO") (pinfunction "LCD_MISO_LCD_MISO") (pintype "bidirectional"))
      (node (ref "U$13") (pin "SD_MISO") (pinfunction "SD_MISO_SD_MISO") (pintype "bidirectional"))
    )
    (net (code "41") (name "LCD_MOSI") (class "Default")
      (node (ref "STM_CHIP") (pin "23") (pinfunction "PA7_23") (pintype "bidirectional"))
      (node (ref "U$13") (pin "LCD_MOSI") (pinfunction "LCD_MOSI_LCD_MOSI") (pintype "bidirectional"))
      (node (ref "U$13") (pin "SD_MOSI") (pinfunction "SD_MOSI_SD_MOSI") (pintype "bidirectional"))
    )
    (net (code "42") (name "LCD_RESET") (class "Default")
      (node (ref "STM_CHIP") (pin "25") (pinfunction "PC5_25") (pintype "bidirectional"))
      (node (ref "U$13") (pin "LCD_RESET") (pinfunction "LCD_RESET_LCD_RESET") (pintype "bidirectional"))
    )
    (net (code "43") (name "LCD_SCK") (class "Default")
      (node (ref "STM_CHIP") (pin "21") (pinfunction "PA5_21") (pintype "bidirectional"))
      (node (ref "U$13") (pin "LCD_SCK") (pinfunction "LCD_SCK_LCD_SCK") (pintype "bidirectional"))
      (node (ref "U$13") (pin "SD_SCK") (pinfunction "SD_SCK_SD_SCK") (pintype "bidirectional"))
    )
    (net (code "44") (name "LINKLED") (class "Default")
      (node (ref "ETH-R5") (pin "1") (pinfunction "1_1") (pintype "passive"))
      (node (ref "U2") (pin "25") (pinfunction "LINKLED_25") (pintype "passive"))
    )
    (net (code "45") (name "MQ2_DATA") (class "Default")
      (node (ref "MQ2-R1") (pin "2") (pinfunction "2_2") (pintype "passive"))
      (node (ref "SENSOR-MQ2") (pin "B1") (pinfunction "B1_B1") (pintype "bidirectional"))
      (node (ref "SENSOR-MQ2") (pin "B2") (pinfunction "B2_B2") (pintype "bidirectional"))
      (node (ref "STM_CHIP") (pin "26") (pinfunction "PB0_26") (pintype "bidirectional"))
    )
    (net (code "46") (name "Net-(ADE-R1-Pad1)") (class "Default")
      (node (ref "ADE-R1") (pin "1") (pinfunction "1_1") (pintype "passive"))
      (node (ref "RTO1") (pin "2") (pinfunction "2_2") (pintype "passive"))
      (node (ref "U$9") (pin "OA") (pinfunction "OA_OA") (pintype "bidirectional"))
    )
    (net (code "47") (name "Net-(ADE-R2-Pad1)") (class "Default")
      (node (ref "ADE-R2") (pin "1") (pinfunction "1_1") (pintype "passive"))
      (node (ref "RTO2") (pin "2") (pinfunction "2_2") (pintype "passive"))
      (node (ref "U$10") (pin "OA") (pinfunction "OA_OA") (pintype "bidirectional"))
    )
    (net (code "48") (name "Net-(ADE-R3-Pad1)") (class "Default")
      (node (ref "ADE-R3") (pin "1") (pinfunction "1_1") (pintype "passive"))
      (node (ref "RTO3") (pin "2") (pinfunction "2_2") (pintype "passive"))
      (node (ref "U$11") (pin "OA") (pinfunction "OA_OA") (pintype "bidirectional"))
    )
    (net (code "49") (name "Net-(ADE-R7-Pad1)") (class "Default")
      (node (ref "ADE-R7") (pin "1") (pinfunction "1_1") (pintype "passive"))
      (node (ref "RTO1") (pin "1") (pinfunction "1_1") (pintype "passive"))
      (node (ref "RTO2") (pin "1") (pinfunction "1_1") (pintype "passive"))
      (node (ref "RTO3") (pin "1") (pinfunction "1_1") (pintype "passive"))
      (node (ref "U$10") (pin "OB") (pinfunction "OB_OB") (pintype "bidirectional"))
      (node (ref "U$11") (pin "OB") (pinfunction "OB_OB") (pintype "bidirectional"))
      (node (ref "U$9") (pin "OB") (pinfunction "OB_OB") (pintype "bidirectional"))
    )
    (net (code "50") (name "Net-(ADE-R8-Pad2)") (class "Default")
      (node (ref "ADE-R8") (pin "2") (pinfunction "2_2") (pintype "passive"))
      (node (ref "ADE-R9") (pin "1") (pinfunction "1_1") (pintype "passive"))
      (node (ref "JP2") (pin "SLEEVE") (pinfunction "SLEEVE_SLEEVE") (pintype "bidirectional"))
    )
    (net (code "51") (name "Net-(ADE-R11-Pad2)") (class "Default")
      (node (ref "ADE-R11") (pin "2") (pinfunction "2_2") (pintype "passive"))
      (node (ref "ADE-R12") (pin "1") (pinfunction "1_1") (pintype "passive"))
      (node (ref "JP3") (pin "SLEEVE") (pinfunction "SLEEVE_SLEEVE") (pintype "bidirectional"))
    )
    (net (code "52") (name "Net-(ADE-R14-Pad2)") (class "Default")
      (node (ref "ADE-R14") (pin "2") (pinfunction "2_2") (pintype "passive"))
      (node (ref "ADE-R15") (pin "1") (pinfunction "1_1") (pintype "passive"))
      (node (ref "JP4") (pin "SLEEVE") (pinfunction "SLEEVE_SLEEVE") (pintype "bidirectional"))
    )
    (net (code "53") (name "Net-(ETHERNET-LED1_K)") (class "Default")
      (node (ref "ETH-R4") (pin "2") (pinfunction "2_2") (pintype "passive"))
      (node (ref "ETHERNET") (pin "10") (pinfunction "LED1_K_10") (pintype "bidirectional"))
    )
    (net (code "54") (name "Net-(ETHERNET-LED2_K)") (class "Default")
      (node (ref "ETH-R5") (pin "2") (pinfunction "2_2") (pintype "passive"))
      (node (ref "ETHERNET") (pin "11") (pinfunction "LED2_K_11") (pintype "bidirectional"))
    )
    (net (code "55") (name "Net-(ETHERNET-RCT)") (class "Default")
      (node (ref "ETH-C3") (pin "2") (pinfunction "2_2") (pintype "passive"))
      (node (ref "ETH-R6") (pin "1") (pinfunction "1_1") (pintype "passive"))
      (node (ref "ETH-R7") (pin "2") (pinfunction "2_2") (pintype "passive"))
      (node (ref "ETHERNET") (pin "6") (pinfunction "RCT_6") (pintype "bidirectional"))
    )
    (net (code "56") (name "Net-(ETHERNET-RX+)") (class "Default")
      (node (ref "ETH-C2") (pin "1") (pinfunction "1_1") (pintype "passive"))
      (node (ref "ETHERNET") (pin "7") (pinfunction "RX+_7") (pintype "bidirectional"))
    )
    (net (code "57") (name "Net-(ETHERNET-RX-)") (class "Default")
      (node (ref "ETH-C4") (pin "1") (pinfunction "1_1") (pintype "passive"))
      (node (ref "ETHERNET") (pin "8") (pinfunction "RX-_8") (pintype "bidirectional"))
    )
    (net (code "58") (name "Net-(ETHERNET-TCT)") (class "Default")
      (node (ref "ETH-C1") (pin "2") (pinfunction "2_2") (pintype "passive"))
      (node (ref "ETH-R3") (pin "1") (pinfunction "1_1") (pintype "passive"))
      (node (ref "ETHERNET") (pin "3") (pinfunction "TCT_3") (pintype "bidirectional"))
    )
    (net (code "59") (name "Net-(IC1-RF_ANT)") (class "Default")
      (node (ref "IC1") (pin "P$60") (pinfunction "RF_ANT_P$60") (pintype "bidirectional"))
      (node (ref "U$7") (pin "P$3") (pinfunction "SIGNAL_P$3") (pintype "bidirectional"))
    )
    (net (code "60") (name "Net-(IC1-SIM_CLK)") (class "Default")
      (node (ref "IC1") (pin "P$32") (pinfunction "SIM_CLK_P$32") (pintype "bidirectional"))
      (node (ref "SIM900-R2") (pin "1") (pinfunction "1_1") (pintype "passive"))
    )
    (net (code "61") (name "Net-(IC1-SIM_DATA)") (class "Default")
      (node (ref "IC1") (pin "P$31") (pinfunction "SIM_DATA_P$31") (pintype "bidirectional"))
      (node (ref "SIM900-R3") (pin "1") (pinfunction "1_1") (pintype "passive"))
    )
    (net (code "62") (name "Net-(IC1-SIM_RST)") (class "Default")
      (node (ref "IC1") (pin "P$33") (pinfunction "SIM_RST_P$33") (pintype "bidirectional"))
      (node (ref "SIM900-R1") (pin "1") (pinfunction "1_1") (pintype "passive"))
    )
    (net (code "63") (name "Net-(IC1-VBAT1)") (class "Default")
      (node (ref "IC1") (pin "P$55") (pinfunction "VBAT1_P$55") (pintype "power_in"))
      (node (ref "IC1") (pin "P$56") (pinfunction "VBAT2_P$56") (pintype "power_in"))
      (node (ref "IC1") (pin "P$57") (pinfunction "VBAT3_P$57") (pintype "power_in"))
      (node (ref "SIM900-C1") (pin "+") (pinfunction "+_+") (pintype "passive"))
      (node (ref "SIM900-C2") (pin "+") (pinfunction "+_+") (pintype "passive"))
      (node (ref "SYS-L2") (pin "1") (pinfunction "1_1") (pintype "passive"))
    )
    (net (code "64") (name "Net-(IC1-VRTC)") (class "Default")
      (node (ref "IC1") (pin "P$26") (pinfunction "VRTC_P$26") (pintype "power_in"))
      (node (ref "SIM900-C3") (pin "1") (pinfunction "1_1") (pintype "passive"))
    )
    (net (code "65") (name "Net-(IC4A-CLKIN)") (class "Default")
      (node (ref "ADE-C3") (pin "1") (pinfunction "1_1") (pintype "passive"))
      (node (ref "ADE-XTAL") (pin "1") (pinfunction "1_1") (pintype "passive"))
      (node (ref "IC4") (pin "19") (pinfunction "CLKIN_19") (pintype "input"))
    )
    (net (code "66") (name "Net-(IC4A-CLKOUT)") (class "Default")
      (node (ref "ADE-C4") (pin "1") (pinfunction "1_1") (pintype "passive"))
      (node (ref "ADE-XTAL") (pin "2") (pinfunction "2_2") (pintype "passive"))
      (node (ref "IC4") (pin "20") (pinfunction "CLKOUT_20") (pintype "output"))
    )
    (net (code "67") (name "Net-(IC4C-IN)") (class "Default")
      (node (ref "ADE-C12") (pin "1") (pinfunction "1_1") (pintype "passive"))
      (node (ref "ADE-R10") (pin "2") (pinfunction "2_2") (pintype "passive"))
      (node (ref "IC4") (pin "6") (pinfunction "IN_6") (pintype "input"))
    )
    (net (code "68") (name "Net-(IC4C-IP)") (class "Default")
      (node (ref "ADE-C11") (pin "1") (pinfunction "1_1") (pintype "passive"))
      (node (ref "ADE-R9") (pin "2") (pinfunction "2_2") (pintype "passive"))
      (node (ref "IC4") (pin "5") (pinfunction "IP_5") (pintype "input"))
    )
    (net (code "69") (name "Net-(IC4D-IN)") (class "Default")
      (node (ref "ADE-C14") (pin "1") (pinfunction "1_1") (pintype "passive"))
      (node (ref "ADE-R13") (pin "2") (pinfunction "2_2") (pintype "passive"))
      (node (ref "IC4") (pin "8") (pinfunction "IN_8") (pintype "input"))
    )
    (net (code "70") (name "Net-(IC4D-IP)") (class "Default")
      (node (ref "ADE-C13") (pin "1") (pinfunction "1_1") (pintype "passive"))
      (node (ref "ADE-R12") (pin "2") (pinfunction "2_2") (pintype "passive"))
      (node (ref "IC4") (pin "7") (pinfunction "IP_7") (pintype "input"))
    )
    (net (code "71") (name "Net-(IC4E-IN)") (class "Default")
      (node (ref "ADE-C16") (pin "1") (pinfunction "1_1") (pintype "passive"))
      (node (ref "ADE-R16") (pin "2") (pinfunction "2_2") (pintype "passive"))
      (node (ref "IC4") (pin "10") (pinfunction "IN_10") (pintype "input"))
    )
    (net (code "72") (name "Net-(IC4E-IP)") (class "Default")
      (node (ref "ADE-C15") (pin "1") (pinfunction "1_1") (pintype "passive"))
      (node (ref "ADE-R15") (pin "2") (pinfunction "2_2") (pintype "passive"))
      (node (ref "IC4") (pin "9") (pinfunction "IP_9") (pintype "input"))
    )
    (net (code "73") (name "Net-(IC4F-REF)") (class "Default")
      (node (ref "ADE-C1") (pin "1") (pinfunction "1_1") (pintype "passive"))
      (node (ref "ADE-C2") (pin "1") (pinfunction "1_1") (pintype "passive"))
      (node (ref "IC4") (pin "12") (pinfunction "REF_12") (pintype "bidirectional"))
    )
    (net (code "74") (name "Net-(IC4G-VAP)") (class "Default")
      (node (ref "ADE-C7") (pin "1") (pinfunction "1_1") (pintype "passive"))
      (node (ref "ADE-R1") (pin "2") (pinfunction "2_2") (pintype "passive"))
      (node (ref "ADE-R4") (pin "2") (pinfunction "2_2") (pintype "passive"))
      (node (ref "IC4") (pin "16") (pinfunction "VAP_16") (pintype "input"))
    )
    (net (code "75") (name "Net-(IC4G-VBP)") (class "Default")
      (node (ref "ADE-C8") (pin "1") (pinfunction "1_1") (pintype "passive"))
      (node (ref "ADE-R2") (pin "2") (pinfunction "2_2") (pintype "passive"))
      (node (ref "ADE-R5") (pin "2") (pinfunction "2_2") (pintype "passive"))
      (node (ref "IC4") (pin "15") (pinfunction "VBP_15") (pintype "input"))
    )
    (net (code "76") (name "Net-(IC4G-VCP)") (class "Default")
      (node (ref "ADE-C9") (pin "1") (pinfunction "1_1") (pintype "passive"))
      (node (ref "ADE-R3") (pin "2") (pinfunction "2_2") (pintype "passive"))
      (node (ref "ADE-R6") (pin "2") (pinfunction "2_2") (pintype "passive"))
      (node (ref "IC4") (pin "14") (pinfunction "VCP_14") (pintype "input"))
    )
    (net (code "77") (name "Net-(IC4G-VN)") (class "Default")
      (node (ref "ADE-C10") (pin "1") (pinfunction "1_1") (pintype "passive"))
      (node (ref "ADE-R7") (pin "2") (pinfunction "2_2") (pintype "passive"))
      (node (ref "IC4") (pin "13") (pinfunction "VN_13") (pintype "input"))
    )
    (net (code "78") (name "Net-(JP2-LEFT)") (class "Default")
      (node (ref "ADE-R10") (pin "1") (pinfunction "1_1") (pintype "passive"))
      (node (ref "ADE-R8") (pin "1") (pinfunction "1_1") (pintype "passive"))
      (node (ref "JP2") (pin "RING") (pinfunction "RIGHT_RING") (pintype "bidirectional"))
      (node (ref "JP2") (pin "TIP") (pinfunction "LEFT_TIP") (pintype "bidirectional"))
    )
    (net (code "79") (name "Net-(JP3-LEFT)") (class "Default")
      (node (ref "ADE-R11") (pin "1") (pinfunction "1_1") (pintype "passive"))
      (node (ref "ADE-R13") (pin "1") (pinfunction "1_1") (pintype "passive"))
      (node (ref "JP3") (pin "RING") (pinfunction "RIGHT_RING") (pintype "bidirectional"))
      (node (ref "JP3") (pin "TIP") (pinfunction "LEFT_TIP") (pintype "bidirectional"))
    )
    (net (code "80") (name "Net-(JP4-LEFT)") (class "Default")
      (node (ref "ADE-R14") (pin "1") (pinfunction "1_1") (pintype "passive"))
      (node (ref "ADE-R16") (pin "1") (pinfunction "1_1") (pintype "passive"))
      (node (ref "JP4") (pin "RING") (pinfunction "RIGHT_RING") (pintype "bidirectional"))
      (node (ref "JP4") (pin "TIP") (pinfunction "LEFT_TIP") (pintype "bidirectional"))
    )
    (net (code "81") (name "Net-(OK1A-A)") (class "Default")
      (node (ref "OK1") (pin "1") (pinfunction "A_1") (pintype "passive"))
      (node (ref "R_CH3") (pin "2") (pinfunction "2_2") (pintype "passive"))
    )
    (net (code "82") (name "Net-(OK1B-A)") (class "Default")
      (node (ref "OK1") (pin "3") (pinfunction "A_3") (pintype "passive"))
      (node (ref "R_CH4") (pin "2") (pinfunction "2_2") (pintype "passive"))
    )
    (net (code "83") (name "Net-(OK2A-A)") (class "Default")
      (node (ref "OK2") (pin "1") (pinfunction "A_1") (pintype "passive"))
      (node (ref "R_CH1") (pin "2") (pinfunction "2_2") (pintype "passive"))
    )
    (net (code "84") (name "Net-(OK2B-A)") (class "Default")
      (node (ref "OK2") (pin "3") (pinfunction "A_3") (pintype "passive"))
      (node (ref "R_CH2") (pin "2") (pinfunction "2_2") (pintype "passive"))
    )
    (net (code "85") (name "Net-(RT1-Pad2)") (class "Default")
      (node (ref "RT1") (pin "2") (pinfunction "2_2") (pintype "passive"))
      (node (ref "U$9") (pin "IA") (pinfunction "IA_IA") (pintype "bidirectional"))
    )
    (net (code "86") (name "Net-(RT2-Pad2)") (class "Default")
      (node (ref "RT2") (pin "2") (pinfunction "2_2") (pintype "passive"))
      (node (ref "U$10") (pin "IA") (pinfunction "IA_IA") (pintype "bidirectional"))
    )
    (net (code "87") (name "Net-(RT3-Pad2)") (class "Default")
      (node (ref "RT3") (pin "2") (pinfunction "2_2") (pintype "passive"))
      (node (ref "U$11") (pin "IA") (pinfunction "IA_IA") (pintype "bidirectional"))
    )
    (net (code "88") (name "Net-(RW5500-1A-2)") (class "Default")
      (node (ref "RW5500-1") (pin "8") (pinfunction "2_8") (pintype "passive"))
      (node (ref "U2") (pin "42") (pinfunction "RSVD_42") (pintype "passive"))
    )
    (net (code "89") (name "Net-(RW5500-1B-2)") (class "Default")
      (node (ref "RW5500-1") (pin "7") (pinfunction "2_7") (pintype "passive"))
      (node (ref "U2") (pin "43") (pinfunction "PMODE2_43") (pintype "passive"))
    )
    (net (code "90") (name "Net-(RW5500-1C-2)") (class "Default")
      (node (ref "RW5500-1") (pin "6") (pinfunction "2_6") (pintype "passive"))
      (node (ref "U2") (pin "44") (pinfunction "PMODE1_44") (pintype "passive"))
    )
    (net (code "91") (name "Net-(RW5500-1D-2)") (class "Default")
      (node (ref "RW5500-1") (pin "5") (pinfunction "2_5") (pintype "passive"))
      (node (ref "U2") (pin "45") (pinfunction "PMODE0_45") (pintype "passive"))
    )
    (net (code "92") (name "Net-(RW5500-2-Pad1)") (class "Default")
      (node (ref "RW5500-2") (pin "1") (pinfunction "1_1") (pintype "passive"))
      (node (ref "U2") (pin "41") (pinfunction "RSVD_41") (pintype "passive"))
    )
    (net (code "93") (name "Net-(RW5500-2B-1)") (class "Default")
      (node (ref "RW5500-2") (pin "2") (pinfunction "1_2") (pintype "passive"))
      (node (ref "U2") (pin "40") (pinfunction "RSVD_40") (pintype "passive"))
    )
    (net (code "94") (name "Net-(RW5500-2C-1)") (class "Default")
      (node (ref "RW5500-2") (pin "3") (pinfunction "1_3") (pintype "passive"))
      (node (ref "U2") (pin "39") (pinfunction "RSVD_39") (pintype "passive"))
    )
    (net (code "95") (name "Net-(RW5500-2D-1)") (class "Default")
      (node (ref "RW5500-2") (pin "4") (pinfunction "1_4") (pintype "passive"))
      (node (ref "U2") (pin "38") (pinfunction "RSVD_38") (pintype "passive"))
    )
    (net (code "96") (name "Net-(SIM900-LED1-PadA)") (class "Default")
      (node (ref "SIM900-LED1") (pin "A") (pinfunction "A_A") (pintype "passive"))
      (node (ref "SIM900-R4") (pin "1") (pinfunction "1_1") (pintype "passive"))
    )
    (net (code "97") (name "Net-(SIM900-LED1-PadC)") (class "Default")
      (node (ref "SIM900-LED1") (pin "C") (pinfunction "C_C") (pintype "passive"))
      (node (ref "SIM900-T1") (pin "C") (pinfunction "C_C") (pintype "passive"))
    )
    (net (code "98") (name "Net-(SIM900-LED2-PadA)") (class "Default")
      (node (ref "SIM900-LED2") (pin "A") (pinfunction "A_A") (pintype "passive"))
      (node (ref "SIM900-R7") (pin "1") (pinfunction "1_1") (pintype "passive"))
    )
    (net (code "99") (name "Net-(SIM900-LED2-PadC)") (class "Default")
      (node (ref "SIM900-LED2") (pin "C") (pinfunction "C_C") (pintype "passive"))
      (node (ref "SIM900-T2") (pin "C") (pinfunction "C_C") (pintype "passive"))
    )
    (net (code "100") (name "Net-(SIM900-R5-Pad1)") (class "Default")
      (node (ref "SIM900-R5") (pin "1") (pinfunction "1_1") (pintype "passive"))
      (node (ref "SIM900-R6") (pin "1") (pinfunction "1_1") (pintype "passive"))
      (node (ref "SIM900-T1") (pin "B") (pinfunction "B_B") (pintype "passive"))
    )
    (net (code "101") (name "Net-(SIM900-R8-Pad1)") (class "Default")
      (node (ref "SIM900-R8") (pin "1") (pinfunction "1_1") (pintype "passive"))
      (node (ref "SIM900-R9") (pin "1") (pinfunction "1_1") (pintype "passive"))
      (node (ref "SIM900-T2") (pin "B") (pinfunction "B_B") (pintype "passive"))
    )
    (net (code "102") (name "Net-(SIM900-R10-Pad2)") (class "Default")
      (node (ref "SIM900-R10") (pin "2") (pinfunction "2_2") (pintype "passive"))
      (node (ref "SIM900-T3") (pin "B") (pinfunction "B_B") (pintype "passive"))
    )
    (net (code "103") (name "Net-(SIM900-R11-Pad2)") (class "Default")
      (node (ref "SIM900-R11") (pin "2") (pinfunction "2_2") (pintype "passive"))
      (node (ref "SIM900-T4") (pin "B") (pinfunction "B_B") (pintype "passive"))
    )
    (net (code "104") (name "Net-(STM_CHIP-PA2)") (class "Default")
      (node (ref "JP_ESP_RX") (pin "2") (pinfunction "2_2") (pintype "passive"))
      (node (ref "STM_CHIP") (pin "16") (pinfunction "PA2_16") (pintype "bidirectional"))
    )
    (net (code "105") (name "Net-(STM_CHIP-PA3)") (class "Default")
      (node (ref "JP_ESP_TX") (pin "2") (pinfunction "2_2") (pintype "passive"))
      (node (ref "STM_CHIP") (pin "17") (pinfunction "PA3_17") (pintype "bidirectional"))
    )
    (net (code "106") (name "Net-(STM_CHIP-PC14-OSC32_IN)") (class "Default")
      (node (ref "STM-C2") (pin "2") (pinfunction "2_2") (pintype "passive"))
      (node (ref "STM-XTAL") (pin "2") (pinfunction "2_2") (pintype "passive"))
      (node (ref "STM_CHIP") (pin "3") (pinfunction "PC14-OSC32_IN_3") (pintype "bidirectional"))
    )
    (net (code "107") (name "Net-(STM_CHIP-PC15-OSC32_OUT)") (class "Default")
      (node (ref "STM-C3") (pin "2") (pinfunction "2_2") (pintype "passive"))
      (node (ref "STM-XTAL") (pin "1") (pinfunction "1_1") (pintype "passive"))
      (node (ref "STM_CHIP") (pin "4") (pinfunction "PC15-OSC32_OUT_4") (pintype "bidirectional"))
    )
    (net (code "108") (name "Net-(U$12-P$1)") (class "Default")
      (node (ref "RT1") (pin "1") (pinfunction "1_1") (pintype "passive"))
      (node (ref "U$12") (pin "P1") (pinfunction "P$1_P1") (pintype "bidirectional"))
    )
    (net (code "109") (name "Net-(U$12-P$2)") (class "Default")
      (node (ref "RT2") (pin "1") (pinfunction "1_1") (pintype "passive"))
      (node (ref "U$12") (pin "P2") (pinfunction "P$2_P2") (pintype "bidirectional"))
    )
    (net (code "110") (name "Net-(U$12-P$3)") (class "Default")
      (node (ref "RT3") (pin "1") (pinfunction "1_1") (pintype "passive"))
      (node (ref "U$12") (pin "P3") (pinfunction "P$3_P3") (pintype "bidirectional"))
    )
    (net (code "111") (name "Net-(U$12-P$4)") (class "Default")
      (node (ref "U$10") (pin "IB") (pinfunction "IB_IB") (pintype "bidirectional"))
      (node (ref "U$11") (pin "IB") (pinfunction "IB_IB") (pintype "bidirectional"))
      (node (ref "U$12") (pin "P4") (pinfunction "P$4_P4") (pintype "bidirectional"))
      (node (ref "U$9") (pin "IB") (pinfunction "IB_IB") (pintype "bidirectional"))
    )
    (net (code "112") (name "Net-(U2-1V2O)") (class "Default")
      (node (ref "U2") (pin "22") (pinfunction "1V2O_22") (pintype "passive"))
      (node (ref "W5500-C4") (pin "1") (pinfunction "1_1") (pintype "passive"))
    )
    (net (code "113") (name "Net-(U2-EXRES1)") (class "Default")
      (node (ref "U2") (pin "10") (pinfunction "EXRES1_10") (pintype "passive"))
      (node (ref "W5500-R12") (pin "2") (pinfunction "2_2") (pintype "passive"))
    )
    (net (code "114") (name "Net-(U2-RSVD-Pad23)") (class "Default")
      (node (ref "U2") (pin "23") (pinfunction "RSVD_23") (pintype "passive"))
      (node (ref "W5500-R11") (pin "2") (pinfunction "2_2") (pintype "passive"))
    )
    (net (code "115") (name "Net-(U2-TOCAP)") (class "Default")
      (node (ref "U2") (pin "20") (pinfunction "TOCAP_20") (pintype "passive"))
      (node (ref "W5500-C3") (pin "1") (pinfunction "1_1") (pintype "passive"))
    )
    (net (code "116") (name "Net-(U2-XI{slash}CLKIN)") (class "Default")
      (node (ref "U$3") (pin "P$1") (pinfunction "P$1_P$1") (pintype "bidirectional"))
      (node (ref "U2") (pin "30") (pinfunction "XI/CLKIN_30") (pintype "passive"))
      (node (ref "W5500-C1") (pin "1") (pinfunction "1_1") (pintype "passive"))
      (node (ref "W5500-R10") (pin "1") (pinfunction "1_1") (pintype "passive"))
      (node (ref "W5500-XTAL") (pin "1") (pinfunction "1_1") (pintype "passive"))
    )
    (net (code "117") (name "Net-(U2-XO)") (class "Default")
      (node (ref "U$3") (pin "P$2") (pinfunction "P$2_P$2") (pintype "bidirectional"))
      (node (ref "U2") (pin "31") (pinfunction "XO_31") (pintype "passive"))
      (node (ref "W5500-C2") (pin "1") (pinfunction "1_1") (pintype "passive"))
      (node (ref "W5500-R10") (pin "2") (pinfunction "2_2") (pintype "passive"))
      (node (ref "W5500-XTAL") (pin "2") (pinfunction "2_2") (pintype "passive"))
    )
    (net (code "118") (name "Q1") (class "Default")
      (node (ref "IC2") (pin "15") (pinfunction "QA_15") (pintype "tri_state"))
      (node (ref "SR_OUT1") (pin "3") (pinfunction "3_3") (pintype "passive"))
    )
    (net (code "119") (name "Q2") (class "Default")
      (node (ref "IC2") (pin "1") (pinfunction "QB_1") (pintype "tri_state"))
      (node (ref "SR_OUT1") (pin "4") (pinfunction "4_4") (pintype "passive"))
    )
    (net (code "120") (name "Q3") (class "Default")
      (node (ref "IC2") (pin "2") (pinfunction "QC_2") (pintype "tri_state"))
      (node (ref "SR_OUT1") (pin "5") (pinfunction "5_5") (pintype "passive"))
    )
    (net (code "121") (name "Q4") (class "Default")
      (node (ref "IC2") (pin "3") (pinfunction "QD_3") (pintype "tri_state"))
      (node (ref "SR_OUT1") (pin "6") (pinfunction "6_6") (pintype "passive"))
    )
    (net (code "122") (name "Q5") (class "Default")
      (node (ref "IC2") (pin "4") (pinfunction "QE_4") (pintype "tri_state"))
      (node (ref "SR_OUT1") (pin "7") (pinfunction "7_7") (pintype "passive"))
    )
    (net (code "123") (name "Q6") (class "Default")
      (node (ref "IC2") (pin "5") (pinfunction "QF_5") (pintype "tri_state"))
      (node (ref "SR_OUT1") (pin "8") (pinfunction "8_8") (pintype "passive"))
    )
    (net (code "124") (name "Q7") (class "Default")
      (node (ref "IC2") (pin "6") (pinfunction "QG_6") (pintype "tri_state"))
      (node (ref "SR_OUT1") (pin "9") (pinfunction "9_9") (pintype "passive"))
    )
    (net (code "125") (name "Q8") (class "Default")
      (node (ref "IC2") (pin "7") (pinfunction "QH_7") (pintype "tri_state"))
      (node (ref "SR_OUT1") (pin "10") (pinfunction "10_10") (pintype "passive"))
    )
    (net (code "126") (name "Q9") (class "Default")
      (node (ref "IC3") (pin "15") (pinfunction "QA_15") (pintype "tri_state"))
      (node (ref "SR_OUT2") (pin "3") (pinfunction "3_3") (pintype "passive"))
    )
    (net (code "127") (name "Q10") (class "Default")
      (node (ref "IC3") (pin "1") (pinfunction "QB_1") (pintype "tri_state"))
      (node (ref "SR_OUT2") (pin "4") (pinfunction "4_4") (pintype "passive"))
    )
    (net (code "128") (name "Q11") (class "Default")
      (node (ref "IC3") (pin "2") (pinfunction "QC_2") (pintype "tri_state"))
      (node (ref "SR_OUT2") (pin "5") (pinfunction "5_5") (pintype "passive"))
    )
    (net (code "129") (name "Q12") (class "Default")
      (node (ref "IC3") (pin "3") (pinfunction "QD_3") (pintype "tri_state"))
      (node (ref "SR_OUT2") (pin "6") (pinfunction "6_6") (pintype "passive"))
    )
    (net (code "130") (name "Q13") (class "Default")
      (node (ref "IC3") (pin "4") (pinfunction "QE_4") (pintype "tri_state"))
      (node (ref "SR_OUT2") (pin "7") (pinfunction "7_7") (pintype "passive"))
    )
    (net (code "131") (name "Q14") (class "Default")
      (node (ref "IC3") (pin "5") (pinfunction "QF_5") (pintype "tri_state"))
      (node (ref "SR_OUT2") (pin "8") (pinfunction "8_8") (pintype "passive"))
    )
    (net (code "132") (name "Q15") (class "Default")
      (node (ref "IC3") (pin "6") (pinfunction "QG_6") (pintype "tri_state"))
      (node (ref "SR_OUT2") (pin "9") (pinfunction "9_9") (pintype "passive"))
    )
    (net (code "133") (name "Q16") (class "Default")
      (node (ref "IC3") (pin "7") (pinfunction "QH_7") (pintype "tri_state"))
      (node (ref "SR_OUT2") (pin "10") (pinfunction "10_10") (pintype "passive"))
    )
    (net (code "134") (name "QS") (class "Default")
      (node (ref "IC2") (pin "9") (pinfunction "QH*_9") (pintype "tri_state"))
      (node (ref "IC3") (pin "14") (pinfunction "SER_14") (pintype "input"))
    )
    (net (code "135") (name "QS2") (class "Default")
      (node (ref "IC3") (pin "9") (pinfunction "QH*_9") (pintype "tri_state"))
      (node (ref "IC5") (pin "14") (pinfunction "SER_14") (pintype "input"))
    )
    (net (code "136") (name "RXN") (class "Default")
      (node (ref "ETH-C4") (pin "2") (pinfunction "2_2") (pintype "passive"))
      (node (ref "ETH-R7") (pin "1") (pinfunction "1_1") (pintype "passive"))
      (node (ref "U2") (pin "5") (pinfunction "RXN_5") (pintype "passive"))
    )
    (net (code "137") (name "RXP") (class "Default")
      (node (ref "ETH-C2") (pin "2") (pinfunction "2_2") (pintype "passive"))
      (node (ref "ETH-R6") (pin "2") (pinfunction "2_2") (pintype "passive"))
      (node (ref "U2") (pin "6") (pinfunction "RXP_6") (pintype "passive"))
    )
    (net (code "138") (name "SD_CS") (class "Default")
      (node (ref "STM_CHIP") (pin "53") (pinfunction "PC12_53") (pintype "bidirectional"))
      (node (ref "U$13") (pin "SD_CS") (pinfunction "SD_CS_SD_CS") (pintype "bidirectional"))
    )
    (net (code "139") (name "SERIAL_RX") (class "Default")
      (node (ref "STM-USART") (pin "3") (pinfunction "3_3") (pintype "passive"))
      (node (ref "STM_CHIP") (pin "43") (pinfunction "PA10_43") (pintype "bidirectional"))
    )
    (net (code "140") (name "SERIAL_TX") (class "Default")
      (node (ref "STM-USART") (pin "2") (pinfunction "2_2") (pintype "passive"))
      (node (ref "STM_CHIP") (pin "42") (pinfunction "PA9_42") (pintype "bidirectional"))
    )
    (net (code "141") (name "SIM900_PWRKEY") (class "Default")
      (node (ref "IC1") (pin "P$1") (pinfunction "PWRKEY_P$1") (pintype "power_in"))
      (node (ref "SIM900-T3") (pin "C") (pinfunction "C_C") (pintype "passive"))
    )
    (net (code "142") (name "SIM900_RESET") (class "Default")
      (node (ref "IC1") (pin "P$16") (pinfunction "NRESET_P$16") (pintype "bidirectional"))
      (node (ref "SIM900-T4") (pin "C") (pinfunction "C_C") (pintype "passive"))
    )
    (net (code "143") (name "SIM_NETLIGHT") (class "Default")
      (node (ref "IC1") (pin "P$52") (pinfunction "NETLIGHT_P$52") (pintype "bidirectional"))
      (node (ref "SIM900-R8") (pin "2") (pinfunction "2_2") (pintype "passive"))
    )
    (net (code "144") (name "SIM_PWRKEY") (class "Default")
      (node (ref "SIM900-R10") (pin "1") (pinfunction "1_1") (pintype "passive"))
      (node (ref "STM_CHIP") (pin "40") (pinfunction "PC9_40") (pintype "bidirectional"))
    )
    (net (code "145") (name "SIM_RESET") (class "Default")
      (node (ref "SIM900-R11") (pin "1") (pinfunction "1_1") (pintype "passive"))
      (node (ref "STM_CHIP") (pin "50") (pinfunction "PA15_50") (pintype "bidirectional"))
    )
    (net (code "146") (name "SIM_RX") (class "Default")
      (node (ref "IC1") (pin "P$10") (pinfunction "RXD_P$10") (pintype "input"))
      (node (ref "STM_CHIP") (pin "51") (pinfunction "PC10_51") (pintype "bidirectional"))
    )
    (net (code "147") (name "SIM_STATUS") (class "Default")
      (node (ref "IC1") (pin "P$66") (pinfunction "STATUS_P$66") (pintype "bidirectional"))
      (node (ref "SIM900-R5") (pin "2") (pinfunction "2_2") (pintype "passive"))
    )
    (net (code "148") (name "SIM_TX") (class "Default")
      (node (ref "IC1") (pin "P$9") (pinfunction "TXD_P$9") (pintype "output"))
      (node (ref "STM_CHIP") (pin "52") (pinfunction "PC11_52") (pintype "bidirectional"))
    )
    (net (code "149") (name "SR_DS") (class "Default")
      (node (ref "IC2") (pin "14") (pinfunction "SER_14") (pintype "input"))
      (node (ref "STM_CHIP") (pin "8") (pinfunction "PC0_8") (pintype "bidirectional"))
    )
    (net (code "150") (name "SR_RST") (class "Default")
      (node (ref "IC2") (pin "10") (pinfunction "SCL_10") (pintype "input"))
      (node (ref "IC3") (pin "10") (pinfunction "SCL_10") (pintype "input"))
      (node (ref "IC5") (pin "10") (pinfunction "SCL_10") (pintype "input"))
      (node (ref "STM_CHIP") (pin "11") (pinfunction "PC3_11") (pintype "bidirectional"))
    )
    (net (code "151") (name "SR_SHCP") (class "Default")
      (node (ref "IC2") (pin "11") (pinfunction "SCK_11") (pintype "input"))
      (node (ref "IC3") (pin "11") (pinfunction "SCK_11") (pintype "input"))
      (node (ref "IC5") (pin "11") (pinfunction "SCK_11") (pintype "input"))
      (node (ref "STM_CHIP") (pin "10") (pinfunction "PC2_10") (pintype "bidirectional"))
    )
    (net (code "152") (name "SR_STCP") (class "Default")
      (node (ref "IC2") (pin "12") (pinfunction "RCK_12") (pintype "input"))
      (node (ref "IC3") (pin "12") (pinfunction "RCK_12") (pintype "input"))
      (node (ref "IC5") (pin "12") (pinfunction "RCK_12") (pintype "input"))
      (node (ref "STM_CHIP") (pin "9") (pinfunction "PC1_9") (pintype "bidirectional"))
    )
    (net (code "153") (name "SWD_NRST") (class "Default")
      (node (ref "S1") (pin "1") (pinfunction "1_1") (pintype "passive"))
      (node (ref "S1") (pin "2") (pinfunction "2_2") (pintype "passive"))
      (node (ref "STM-C8") (pin "1") (pinfunction "1_1") (pintype "passive"))
      (node (ref "STM_CHIP") (pin "7") (pinfunction "NRST_7") (pintype "bidirectional"))
    )
    (net (code "154") (name "SWD_TCK") (class "Default")
      (node (ref "STM-SWD") (pin "2") (pinfunction "2_2") (pintype "passive"))
      (node (ref "STM_CHIP") (pin "49") (pinfunction "PA14_49") (pintype "bidirectional"))
    )
    (net (code "155") (name "SWD_TMS") (class "Default")
      (node (ref "STM-SWD") (pin "4") (pinfunction "4_4") (pintype "passive"))
      (node (ref "STM_CHIP") (pin "46") (pinfunction "PA13_46") (pintype "bidirectional"))
    )
    (net (code "156") (name "TXN") (class "Default")
      (node (ref "ETH-R2") (pin "1") (pinfunction "1_1") (pintype "passive"))
      (node (ref "ETHERNET") (pin "2") (pinfunction "TX-_2") (pintype "bidirectional"))
      (node (ref "U2") (pin "1") (pinfunction "TXN_1") (pintype "passive"))
    )
    (net (code "157") (name "TXP") (class "Default")
      (node (ref "ETH-R1") (pin "1") (pinfunction "1_1") (pintype "passive"))
      (node (ref "ETHERNET") (pin "1") (pinfunction "TX+_1") (pintype "bidirectional"))
      (node (ref "U2") (pin "2") (pinfunction "TXP_2") (pintype "passive"))
    )
    (net (code "158") (name "T_CLK") (class "Default")
      (node (ref "STM_CHIP") (pin "27") (pinfunction "PB1_27") (pintype "bidirectional"))
      (node (ref "U$13") (pin "T_CLK") (pinfunction "T_CLK_T_CLK") (pintype "bidirectional"))
    )
    (net (code "159") (name "T_DIN") (class "Default")
      (node (ref "STM_CHIP") (pin "45") (pinfunction "PA12_45") (pintype "bidirectional"))
      (node (ref "U$13") (pin "T_DIN") (pinfunction "T_DIN_T_DIN") (pintype "bidirectional"))
    )
    (net (code "160") (name "T_DO") (class "Default")
      (node (ref "STM_CHIP") (pin "44") (pinfunction "PA11_44") (pintype "bidirectional"))
      (node (ref "U$13") (pin "T_DO") (pinfunction "T_DO_T_DO") (pintype "bidirectional"))
    )
    (net (code "161") (name "T_IRQ") (class "Default")
      (node (ref "STM_CHIP") (pin "41") (pinfunction "PA8_41") (pintype "bidirectional"))
      (node (ref "U$13") (pin "T_IRQ") (pinfunction "T_IRQ_T_IRQ") (pintype "bidirectional"))
    )
    (net (code "162") (name "USIM_CLK") (class "Default")
      (node (ref "SIM900-R2") (pin "2") (pinfunction "2_2") (pintype "passive"))
      (node (ref "U$8") (pin "SIM_CLK") (pinfunction "SIM_CLK_SIM_CLK") (pintype "bidirectional"))
    )
    (net (code "163") (name "USIM_DATA") (class "Default")
      (node (ref "SIM900-R3") (pin "2") (pinfunction "2_2") (pintype "passive"))
      (node (ref "U$8") (pin "SIM_IO") (pinfunction "SIM_IO_SIM_IO") (pintype "bidirectional"))
    )
    (net (code "164") (name "USIM_RESET") (class "Default")
      (node (ref "SIM900-R1") (pin "2") (pinfunction "2_2") (pintype "passive"))
      (node (ref "U$8") (pin "SIM_RST") (pinfunction "SIM_RST_SIM_RST") (pintype "bidirectional"))
    )
    (net (code "165") (name "USIM_VCC") (class "Default")
      (node (ref "IC1") (pin "P$30") (pinfunction "SIM_VDD_P$30") (pintype "power_in"))
      (node (ref "SIM900-C4") (pin "1") (pinfunction "1_1") (pintype "passive"))
      (node (ref "SIM900-C5") (pin "1") (pinfunction "1_1") (pintype "passive"))
      (node (ref "SIM_C1") (pin "2") (pinfunction "2_2") (pintype "passive"))
      (node (ref "SIM_C2") (pin "2") (pinfunction "2_2") (pintype "passive"))
      (node (ref "U$8") (pin "SIM_VDD") (pinfunction "SIM_VDD_SIM_VDD") (pintype "bidirectional"))
    )
    (net (code "166") (name "VBAT") (class "Default")
      (node (ref "BAT1") (pin "PWR@1") (pinfunction "+_PWR@1") (pintype "power_in"))
      (node (ref "STM_CHIP") (pin "1") (pinfunction "VLCD_1") (pintype "power_in"))
    )
    (net (code "167") (name "VCC") (class "Default")
      (node (ref "ETH-R1") (pin "2") (pinfunction "2_2") (pintype "passive"))
      (node (ref "ETH-R2") (pin "2") (pinfunction "2_2") (pintype "passive"))
      (node (ref "ETH-R3") (pin "2") (pinfunction "2_2") (pintype "passive"))
      (node (ref "STM-C9") (pin "1") (pinfunction "1_1") (pintype "passive"))
      (node (ref "STM-L1") (pin "2") (pinfunction "2_2") (pintype "passive"))
      (node (ref "STM_CHIP") (pin "13") (pinfunction "VDDA_13") (pintype "power_in"))
      (node (ref "SYS-C4") (pin "1") (pinfunction "1_1") (pintype "passive"))
      (node (ref "SYS-R2") (pin "2") (pinfunction "2_2") (pintype "passive"))
      (node (ref "U2") (pin "11") (pinfunction "AVDD_11") (pintype "passive"))
      (node (ref "U2") (pin "15") (pinfunction "AVDD_15") (pintype "passive"))
      (node (ref "U2") (pin "17") (pinfunction "AVDD_17") (pintype "passive"))
      (node (ref "U2") (pin "21") (pinfunction "AVDD_21") (pintype "passive"))
      (node (ref "U2") (pin "4") (pinfunction "AVDD_4") (pintype "passive"))
      (node (ref "U2") (pin "8") (pinfunction "AVDD_8") (pintype "passive"))
      (node (ref "W5500-C10") (pin "1") (pinfunction "1_1") (pintype "passive"))
      (node (ref "W5500-C11") (pin "1") (pinfunction "1_1") (pintype "passive"))
      (node (ref "W5500-C12") (pin "+") (pinfunction "+_+") (pintype "passive"))
      (node (ref "W5500-C6") (pin "1") (pinfunction "1_1") (pintype "passive"))
      (node (ref "W5500-C7") (pin "1") (pinfunction "1_1") (pintype "passive"))
      (node (ref "W5500-C8") (pin "1") (pinfunction "1_1") (pintype "passive"))
      (node (ref "W5500-C9") (pin "1") (pinfunction "1_1") (pintype "passive"))
    )
    (net (code "168") (name "VDD") (class "Default")
      (node (ref "DHT-R1") (pin "1") (pinfunction "1_1") (pintype "passive"))
      (node (ref "ESP_EXT") (pin "1") (pinfunction "1_1") (pintype "passive"))
      (node (ref "ETHERNET") (pin "12") (pinfunction "LED2_A_12") (pintype "bidirectional"))
      (node (ref "ETHERNET") (pin "9") (pinfunction "LED1_A_9") (pintype "bidirectional"))
      (node (ref "IC2") (pin "16") (pinfunction "VCC_16") (pintype "power_in"))
      (node (ref "IC3") (pin "16") (pinfunction "VCC_16") (pintype "power_in"))
      (node (ref "IC5") (pin "16") (pinfunction "VCC_16") (pintype "power_in"))
      (node (ref "LCD-R1") (pin "2") (pinfunction "2_2") (pintype "passive"))
      (node (ref "PWR-SWT") (pin "1") (pinfunction "1_1") (pintype "passive"))
      (node (ref "RW5500-1") (pin "2") (pinfunction "1_2") (pintype "passive"))
      (node (ref "RW5500-1") (pin "3") (pinfunction "1_3") (pintype "passive"))
      (node (ref "RW5500-1") (pin "4") (pinfunction "1_4") (pintype "passive"))
      (node (ref "RW5500-3") (pin "1") (pinfunction "1_1") (pintype "passive"))
      (node (ref "SENSOR-DHT") (pin "1") (pinfunction "1_1") (pintype "passive"))
      (node (ref "SIM900-R4") (pin "2") (pinfunction "2_2") (pintype "passive"))
      (node (ref "SIM900-R7") (pin "2") (pinfunction "2_2") (pintype "passive"))
      (node (ref "STM-C1") (pin "2") (pinfunction "2_2") (pintype "passive"))
      (node (ref "STM-C10") (pin "1") (pinfunction "1_1") (pintype "passive"))
      (node (ref "STM-C11") (pin "1") (pinfunction "1_1") (pintype "passive"))
      (node (ref "STM-C12") (pin "1") (pinfunction "1_1") (pintype "passive"))
      (node (ref "STM-C13") (pin "1") (pinfunction "1_1") (pintype "passive"))
      (node (ref "STM-L1") (pin "1") (pinfunction "1_1") (pintype "passive"))
      (node (ref "STM-SWD") (pin "1") (pinfunction "1_1") (pintype "passive"))
      (node (ref "STM-USART") (pin "1") (pinfunction "1_1") (pintype "passive"))
      (node (ref "STM_CHIP") (pin "19") (pinfunction "VDD_4_19") (pintype "power_in"))
      (node (ref "STM_CHIP") (pin "32") (pinfunction "VDD_1_32") (pintype "power_in"))
      (node (ref "STM_CHIP") (pin "48") (pinfunction "VDD_2_48") (pintype "power_in"))
      (node (ref "STM_CHIP") (pin "64") (pinfunction "VDD_3_64") (pintype "power_in"))
      (node (ref "SYS-C3") (pin "1") (pinfunction "1_1") (pintype "passive"))
      (node (ref "SYS-L2") (pin "2") (pinfunction "2_2") (pintype "passive"))
      (node (ref "SYS-R2") (pin "1") (pinfunction "1_1") (pintype "passive"))
      (node (ref "U$13") (pin "LCD_VCC") (pinfunction "LCD_VCC_LCD_VCC") (pintype "power_in"))
      (node (ref "U2") (pin "28") (pinfunction "VDD_28") (pintype "passive"))
      (node (ref "W5500-C13") (pin "+") (pinfunction "+_+") (pintype "passive"))
      (node (ref "W5500-C5") (pin "1") (pinfunction "1_1") (pintype "passive"))
      (node (ref "W5500-R13") (pin "2") (pinfunction "2_2") (pintype "passive"))
    )
    (net (code "169") (name "VESP") (class "Default")
      (node (ref "ESP-C1") (pin "1") (pinfunction "1_1") (pintype "passive"))
      (node (ref "ESP-GPIO0") (pin "1") (pinfunction "1_1") (pintype "passive"))
      (node (ref "ESP_EXT") (pin "2") (pinfunction "2_2") (pintype "passive"))
      (node (ref "U$5") (pin "CH_PD") (pinfunction "CH_PD_CH_PD") (pintype "bidirectional"))
      (node (ref "U$5") (pin "GPIO02") (pinfunction "GPIO2_GPIO02") (pintype "bidirectional"))
      (node (ref "U$5") (pin "REST") (pinfunction "REST_REST") (pintype "bidirectional"))
      (node (ref "U$5") (pin "VCC") (pinfunction "VCC_VCC") (pintype "power_in"))
    )
    (net (code "170") (name "unconnected-(IC1-ADC-PadP$25)") (class "Default")
      (node (ref "IC1") (pin "P$25") (pinfunction "ADC_P$25") (pintype "bidirectional"))
    )
    (net (code "171") (name "unconnected-(IC1-CTS-PadP$7)") (class "Default")
      (node (ref "IC1") (pin "P$7") (pinfunction "CTS_P$7") (pintype "output"))
    )
    (net (code "172") (name "unconnected-(IC1-DBG_RXD-PadP$28)") (class "Default")
      (node (ref "IC1") (pin "P$28") (pinfunction "DBG_RXD_P$28") (pintype "input"))
    )
    (net (code "173") (name "unconnected-(IC1-DBG_TXD-PadP$27)") (class "Default")
      (node (ref "IC1") (pin "P$27") (pinfunction "DBG_TXD_P$27") (pintype "output"))
    )
    (net (code "174") (name "unconnected-(IC1-DCD-PadP$5)") (class "Default")
      (node (ref "IC1") (pin "P$5") (pinfunction "DCD_P$5") (pintype "output"))
    )
    (net (code "175") (name "unconnected-(IC1-DISP_CLK-PadP$11)") (class "Default")
      (node (ref "IC1") (pin "P$11") (pinfunction "DISP_CLK_P$11") (pintype "bidirectional"))
    )
    (net (code "176") (name "unconnected-(IC1-DISP_CS-PadP$14)") (class "Default")
      (node (ref "IC1") (pin "P$14") (pinfunction "DISP_CS_P$14") (pintype "bidirectional"))
    )
    (net (code "177") (name "unconnected-(IC1-DISP_DATA-PadP$12)") (class "Default")
      (node (ref "IC1") (pin "P$12") (pinfunction "DISP_DATA_P$12") (pintype "bidirectional"))
    )
    (net (code "178") (name "unconnected-(IC1-DISP_DC-PadP$13)") (class "Default")
      (node (ref "IC1") (pin "P$13") (pinfunction "DISP_DC_P$13") (pintype "bidirectional"))
    )
    (net (code "179") (name "unconnected-(IC1-DTR-PadP$3)") (class "Default")
      (node (ref "IC1") (pin "P$3") (pinfunction "DTR_P$3") (pintype "input"))
    )
    (net (code "180") (name "unconnected-(IC1-GPIO1{slash}KBR4-PadP$40)") (class "Default")
      (node (ref "IC1") (pin "P$40") (pinfunction "GPIO1/KBR4_P$40") (pintype "bidirectional"))
    )
    (net (code "181") (name "unconnected-(IC1-GPIO2{slash}KBR3-PadP$41)") (class "Default")
      (node (ref "IC1") (pin "P$41") (pinfunction "GPIO2/KBR3_P$41") (pintype "bidirectional"))
    )
    (net (code "182") (name "unconnected-(IC1-GPIO3{slash}KBR2-PadP$42)") (class "Default")
      (node (ref "IC1") (pin "P$42") (pinfunction "GPIO3/KBR2_P$42") (pintype "bidirectional"))
    )
    (net (code "183") (name "unconnected-(IC1-GPIO4{slash}KBR1-PadP$43)") (class "Default")
      (node (ref "IC1") (pin "P$43") (pinfunction "GPIO4/KBR1_P$43") (pintype "bidirectional"))
    )
    (net (code "184") (name "unconnected-(IC1-GPIO5{slash}KBR0-PadP$44)") (class "Default")
      (node (ref "IC1") (pin "P$44") (pinfunction "GPIO5/KBR0_P$44") (pintype "bidirectional"))
    )
    (net (code "185") (name "unconnected-(IC1-GPIO6{slash}KBC4-PadP$47)") (class "Default")
      (node (ref "IC1") (pin "P$47") (pinfunction "GPIO6/KBC4_P$47") (pintype "bidirectional"))
    )
    (net (code "186") (name "unconnected-(IC1-GPIO7{slash}KBC3-PadP$48)") (class "Default")
      (node (ref "IC1") (pin "P$48") (pinfunction "GPIO7/KBC3_P$48") (pintype "bidirectional"))
    )
    (net (code "187") (name "unconnected-(IC1-GPIO8{slash}KBC2-PadP$49)") (class "Default")
      (node (ref "IC1") (pin "P$49") (pinfunction "GPIO8/KBC2_P$49") (pintype "bidirectional"))
    )
    (net (code "188") (name "unconnected-(IC1-GPIO9{slash}KBC1-PadP$50)") (class "Default")
      (node (ref "IC1") (pin "P$50") (pinfunction "GPIO9/KBC1_P$50") (pintype "bidirectional"))
    )
    (net (code "189") (name "unconnected-(IC1-GPIO10-PadP$51)") (class "Default")
      (node (ref "IC1") (pin "P$51") (pinfunction "GPIO10_P$51") (pintype "bidirectional"))
    )
    (net (code "190") (name "unconnected-(IC1-LINEIN_L-PadP$24)") (class "Default")
      (node (ref "IC1") (pin "P$24") (pinfunction "LINEIN_L_P$24") (pintype "bidirectional"))
    )
    (net (code "191") (name "unconnected-(IC1-LINEIN_R-PadP$23)") (class "Default")
      (node (ref "IC1") (pin "P$23") (pinfunction "LINEIN_R_P$23") (pintype "bidirectional"))
    )
    (net (code "192") (name "unconnected-(IC1-MIC_N-PadP$20)") (class "Default")
      (node (ref "IC1") (pin "P$20") (pinfunction "MIC_N_P$20") (pintype "bidirectional"))
    )
    (net (code "193") (name "unconnected-(IC1-MIC_P-PadP$19)") (class "Default")
      (node (ref "IC1") (pin "P$19") (pinfunction "MIC_P_P$19") (pintype "bidirectional"))
    )
    (net (code "194") (name "unconnected-(IC1-NC-PadP$2)") (class "Default")
      (node (ref "IC1") (pin "P$2") (pinfunction "NC_P$2") (pintype "no_connect"))
    )
    (net (code "195") (name "unconnected-(IC1-NC-PadP$6)") (class "Default")
      (node (ref "IC1") (pin "P$6") (pinfunction "NC_P$6") (pintype "no_connect"))
    )
    (net (code "196") (name "unconnected-(IC1-PWM1-PadP$35)") (class "Default")
      (node (ref "IC1") (pin "P$35") (pinfunction "PWM1_P$35") (pintype "bidirectional"))
    )
    (net (code "197") (name "unconnected-(IC1-PWM2-PadP$36)") (class "Default")
      (node (ref "IC1") (pin "P$36") (pinfunction "PWM2_P$36") (pintype "bidirectional"))
    )
    (net (code "198") (name "unconnected-(IC1-RI-PadP$4)") (class "Default")
      (node (ref "IC1") (pin "P$4") (pinfunction "RI_P$4") (pintype "output"))
    )
    (net (code "199") (name "unconnected-(IC1-RTS-PadP$8)") (class "Default")
      (node (ref "IC1") (pin "P$8") (pinfunction "RTS_P$8") (pintype "input"))
    )
    (net (code "200") (name "unconnected-(IC1-SCL-PadP$38)") (class "Default")
      (node (ref "IC1") (pin "P$38") (pinfunction "SCL_P$38") (pintype "bidirectional"))
    )
    (net (code "201") (name "unconnected-(IC1-SDA-PadP$37)") (class "Default")
      (node (ref "IC1") (pin "P$37") (pinfunction "SDA_P$37") (pintype "bidirectional"))
    )
    (net (code "202") (name "unconnected-(IC1-SIM_PRESENCE-PadP$34)") (class "Default")
      (node (ref "IC1") (pin "P$34") (pinfunction "SIM_PRESENCE_P$34") (pintype "bidirectional"))
    )
    (net (code "203") (name "unconnected-(IC1-SPK_N-PadP$22)") (class "Default")
      (node (ref "IC1") (pin "P$22") (pinfunction "SPK_N_P$22") (pintype "bidirectional"))
    )
    (net (code "204") (name "unconnected-(IC1-SPK_P-PadP$21)") (class "Default")
      (node (ref "IC1") (pin "P$21") (pinfunction "SPK_P_P$21") (pintype "bidirectional"))
    )
    (net (code "205") (name "unconnected-(IC1-VDD_EXT-PadP$15)") (class "Default")
      (node (ref "IC1") (pin "P$15") (pinfunction "VDD_EXT_P$15") (pintype "bidirectional"))
    )
    (net (code "206") (name "unconnected-(IC5A-QE-Pad4)") (class "Default")
      (node (ref "IC5") (pin "4") (pinfunction "QE_4") (pintype "tri_state"))
    )
    (net (code "207") (name "unconnected-(IC5A-QF-Pad5)") (class "Default")
      (node (ref "IC5") (pin "5") (pinfunction "QF_5") (pintype "tri_state"))
    )
    (net (code "208") (name "unconnected-(IC5A-QG-Pad6)") (class "Default")
      (node (ref "IC5") (pin "6") (pinfunction "QG_6") (pintype "tri_state"))
    )
    (net (code "209") (name "unconnected-(IC5A-QH*-Pad9)") (class "Default")
      (node (ref "IC5") (pin "9") (pinfunction "QH*_9") (pintype "tri_state"))
    )
    (net (code "210") (name "unconnected-(IC5A-QH-Pad7)") (class "Default")
      (node (ref "IC5") (pin "7") (pinfunction "QH_7") (pintype "tri_state"))
    )
    (net (code "211") (name "unconnected-(SENSOR-DHT-Pad3)") (class "Default")
      (node (ref "SENSOR-DHT") (pin "3") (pinfunction "3_3") (pintype "passive"))
    )
    (net (code "212") (name "unconnected-(STM_CHIP-BOOT0-Pad60)") (class "Default")
      (node (ref "STM_CHIP") (pin "60") (pinfunction "BOOT0_60") (pintype "input"))
    )
    (net (code "213") (name "unconnected-(STM_CHIP-PA0-WKUP1-Pad14)") (class "Default")
      (node (ref "STM_CHIP") (pin "14") (pinfunction "PA0-WKUP1_14") (pintype "bidirectional"))
    )
    (net (code "214") (name "unconnected-(STM_CHIP-PB2-Pad28)") (class "Default")
      (node (ref "STM_CHIP") (pin "28") (pinfunction "PB2_28") (pintype "bidirectional"))
    )
    (net (code "215") (name "unconnected-(STM_CHIP-PB3-Pad55)") (class "Default")
      (node (ref "STM_CHIP") (pin "55") (pinfunction "PB3_55") (pintype "bidirectional"))
    )
    (net (code "216") (name "unconnected-(STM_CHIP-PB10-Pad29)") (class "Default")
      (node (ref "STM_CHIP") (pin "29") (pinfunction "PB10_29") (pintype "bidirectional"))
    )
    (net (code "217") (name "unconnected-(STM_CHIP-PB11-Pad30)") (class "Default")
      (node (ref "STM_CHIP") (pin "30") (pinfunction "PB11_30") (pintype "bidirectional"))
    )
    (net (code "218") (name "unconnected-(STM_CHIP-PC7-Pad38)") (class "Default")
      (node (ref "STM_CHIP") (pin "38") (pinfunction "PC7_38") (pintype "bidirectional"))
    )
    (net (code "219") (name "unconnected-(STM_CHIP-PC8-Pad39)") (class "Default")
      (node (ref "STM_CHIP") (pin "39") (pinfunction "PC8_39") (pintype "bidirectional"))
    )
    (net (code "220") (name "unconnected-(STM_CHIP-PC13-RTC_AF1-WKUP2-Pad2)") (class "Default")
      (node (ref "STM_CHIP") (pin "2") (pinfunction "PC13-RTC_AF1-WKUP2_2") (pintype "bidirectional"))
    )
    (net (code "221") (name "unconnected-(STM_CHIP-PH0_-OSC_IN-Pad5)") (class "Default")
      (node (ref "STM_CHIP") (pin "5") (pinfunction "PH0_-OSC_IN_5") (pintype "bidirectional"))
    )
    (net (code "222") (name "unconnected-(STM_CHIP-PH1-_OSC_OUT-Pad6)") (class "Default")
      (node (ref "STM_CHIP") (pin "6") (pinfunction "PH1-_OSC_OUT_6") (pintype "bidirectional"))
    )
    (net (code "223") (name "unconnected-(U$5-GPIO4-PadGPIO04)") (class "Default")
      (node (ref "U$5") (pin "GPIO04") (pinfunction "GPIO4_GPIO04") (pintype "bidirectional"))
    )
    (net (code "224") (name "unconnected-(U$5-GPIO5-PadGPIO05)") (class "Default")
      (node (ref "U$5") (pin "GPIO05") (pinfunction "GPIO5_GPIO05") (pintype "bidirectional"))
    )
    (net (code "225") (name "unconnected-(U$5-PadADC)") (class "Default")
      (node (ref "U$5") (pin "ADC") (pinfunction "ADC_ADC") (pintype "bidirectional"))
    )
    (net (code "226") (name "unconnected-(U$5-PadGPIO12)") (class "Default")
      (node (ref "U$5") (pin "GPIO12") (pinfunction "GPIO12_GPIO12") (pintype "bidirectional"))
    )
    (net (code "227") (name "unconnected-(U$5-PadGPIO13)") (class "Default")
      (node (ref "U$5") (pin "GPIO13") (pinfunction "GPIO13_GPIO13") (pintype "bidirectional"))
    )
    (net (code "228") (name "unconnected-(U$5-PadGPIO14)") (class "Default")
      (node (ref "U$5") (pin "GPIO14") (pinfunction "GPIO14_GPIO14") (pintype "bidirectional"))
    )
    (net (code "229") (name "unconnected-(U$5-PadGPIO16)") (class "Default")
      (node (ref "U$5") (pin "GPIO16") (pinfunction "GPIO16_GPIO16") (pintype "bidirectional"))
    )
    (net (code "230") (name "unconnected-(U$8-PadVPP)") (class "Default")
      (node (ref "U$8") (pin "VPP") (pinfunction "VPP_VPP") (pintype "bidirectional"))
    )
    (net (code "231") (name "unconnected-(U2-DNC-Pad7)") (class "Default")
      (node (ref "U2") (pin "7") (pinfunction "DNC_7") (pintype "passive"))
    )
    (net (code "232") (name "unconnected-(U2-DUPLED-Pad26)") (class "Default")
      (node (ref "U2") (pin "26") (pinfunction "DUPLED_26") (pintype "passive"))
    )
    (net (code "233") (name "unconnected-(U2-INT_N-Pad36)") (class "Default")
      (node (ref "U2") (pin "36") (pinfunction "INT_N_36") (pintype "passive"))
    )
    (net (code "234") (name "unconnected-(U2-NC-Pad12)") (class "Default")
      (node (ref "U2") (pin "12") (pinfunction "NC_12") (pintype "passive"))
    )
    (net (code "235") (name "unconnected-(U2-NC-Pad13)") (class "Default")
      (node (ref "U2") (pin "13") (pinfunction "NC_13") (pintype "passive"))
    )
    (net (code "236") (name "unconnected-(U2-NC-Pad46)") (class "Default")
      (node (ref "U2") (pin "46") (pinfunction "NC_46") (pintype "passive"))
    )
    (net (code "237") (name "unconnected-(U2-NC-Pad47)") (class "Default")
      (node (ref "U2") (pin "47") (pinfunction "NC_47") (pintype "passive"))
    )
    (net (code "238") (name "unconnected-(U2-SPDLED-Pad24)") (class "Default")
      (node (ref "U2") (pin "24") (pinfunction "SPDLED_24") (pintype "passive"))
    )
    (net (code "239") (name "unconnected-(U2-VBG-Pad18)") (class "Default")
      (node (ref "U2") (pin "18") (pinfunction "VBG_18") (pintype "passive"))
    )
  )
)
